# V3_0.net
KiCad netlist of a schematic drawn in Altium Designer
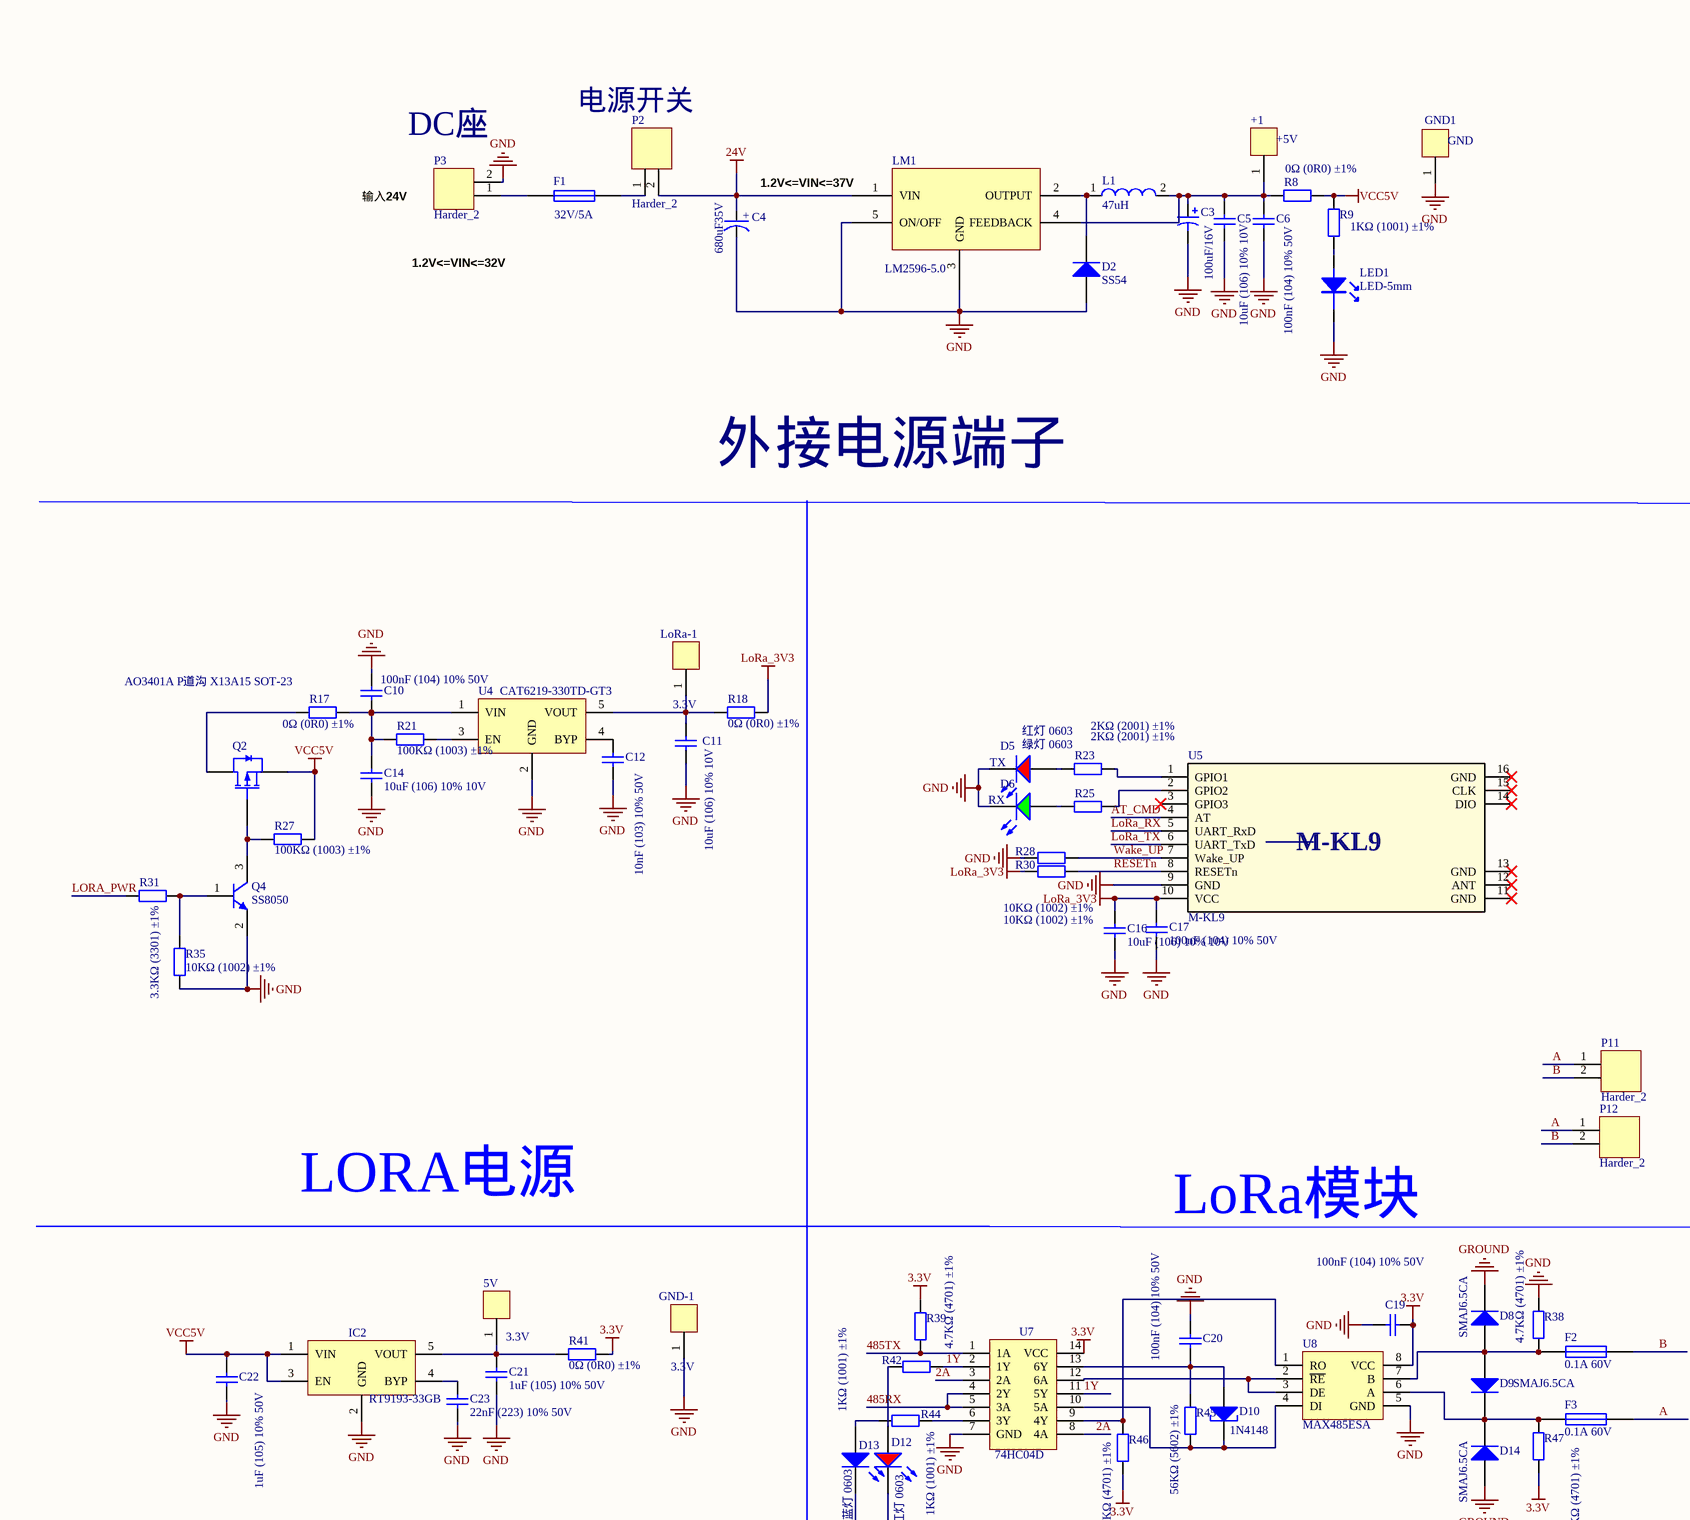
[diagram p0: 电磁阀V3.0.SchDoc, top left]
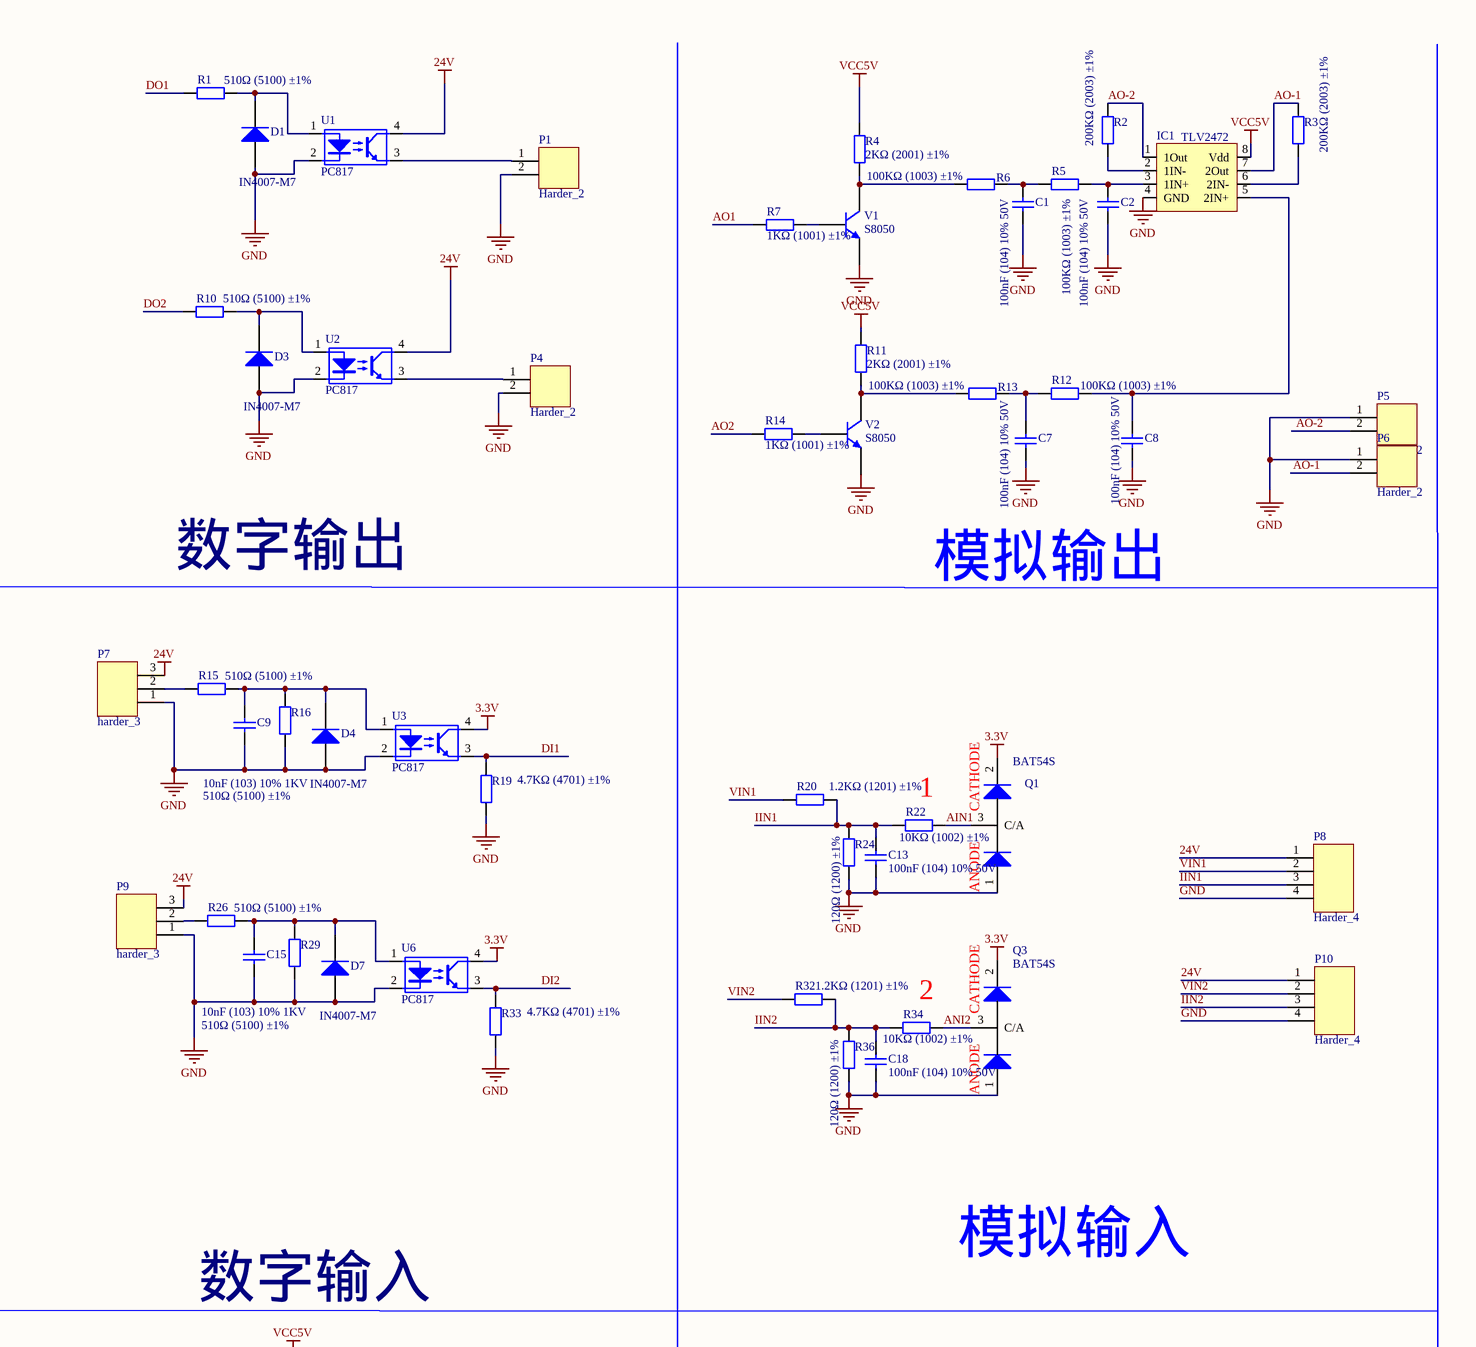
[diagram p1: 电磁阀V3.0.SchDoc, top right]
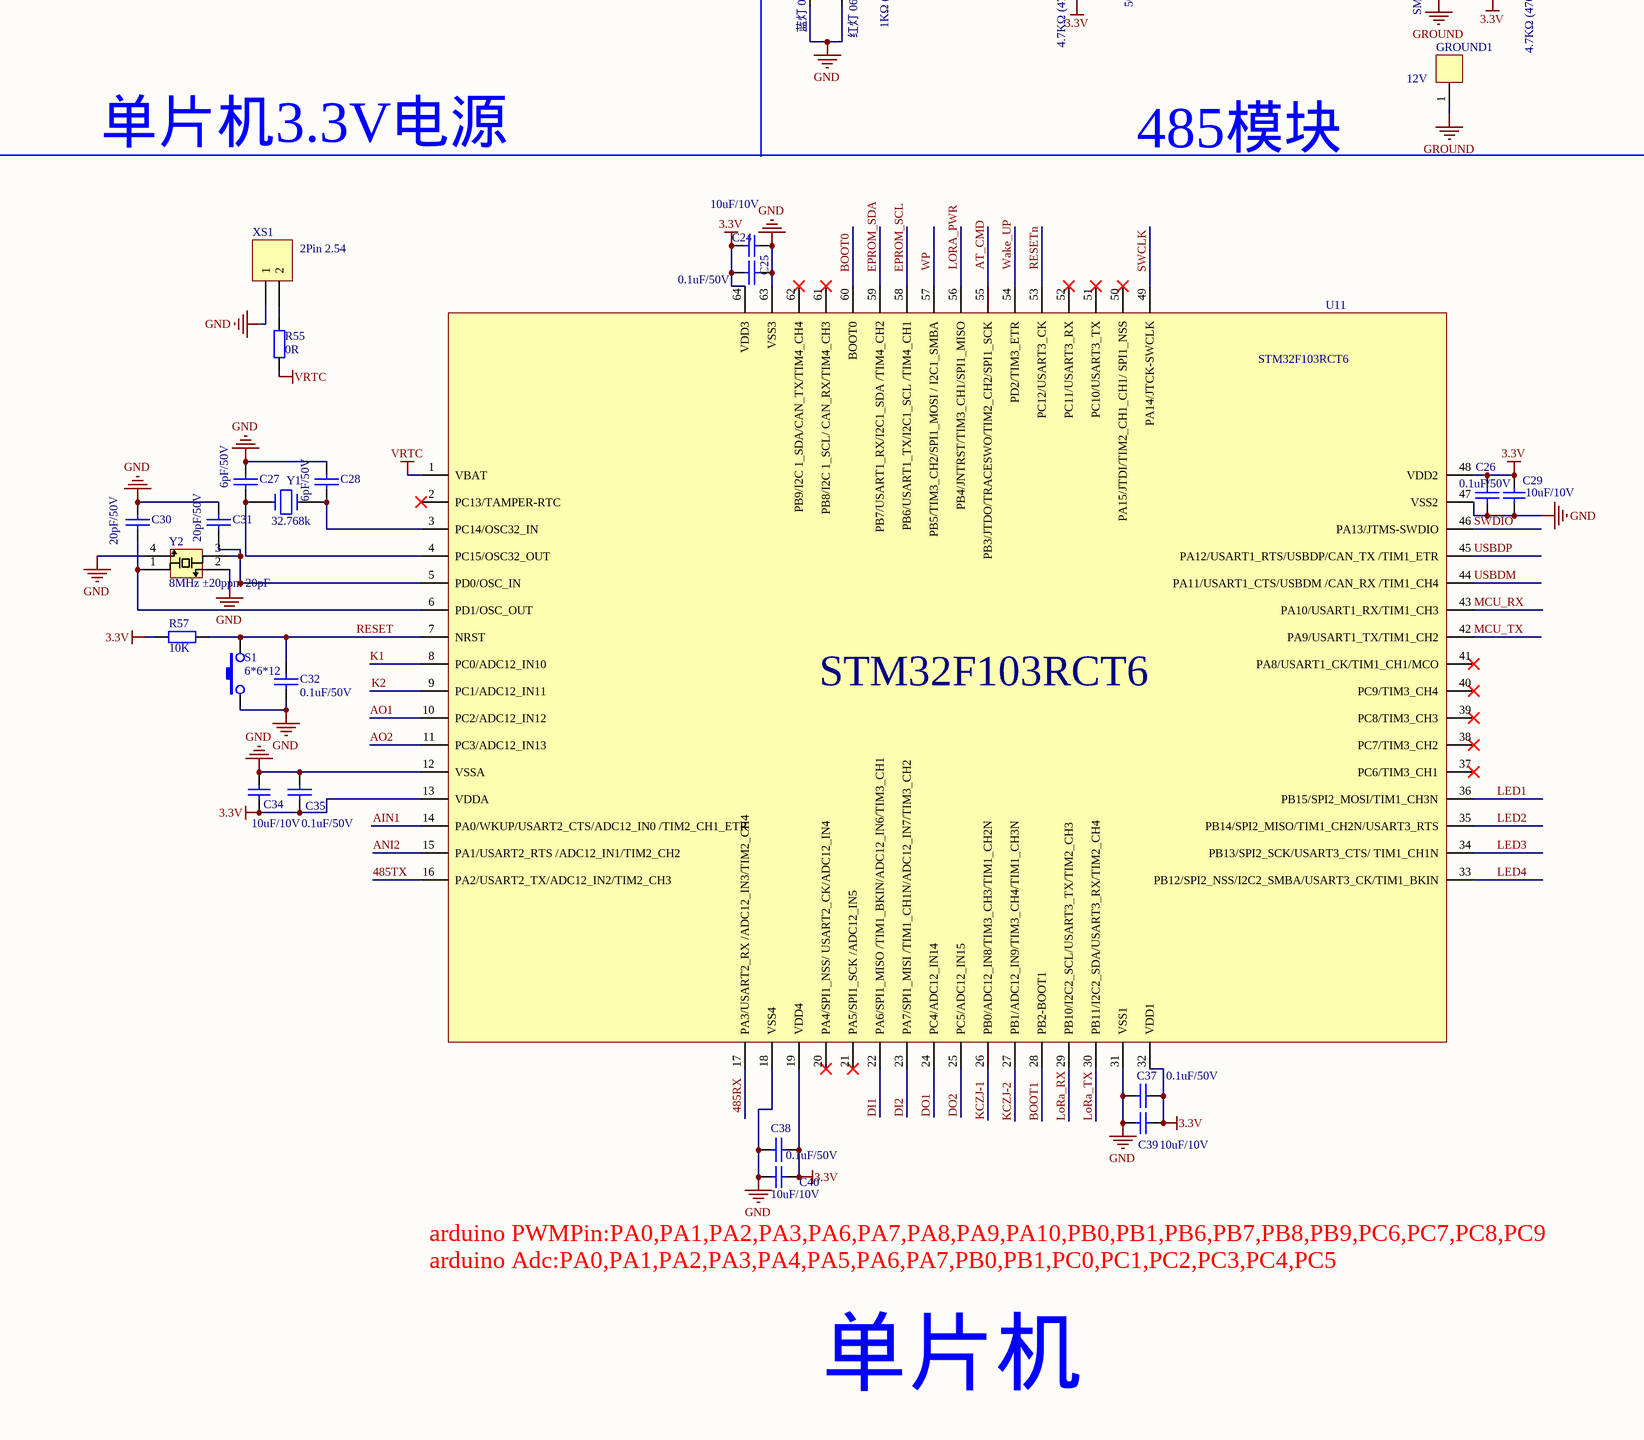
[diagram p2: 电磁阀V3.0.SchDoc, bottom left]
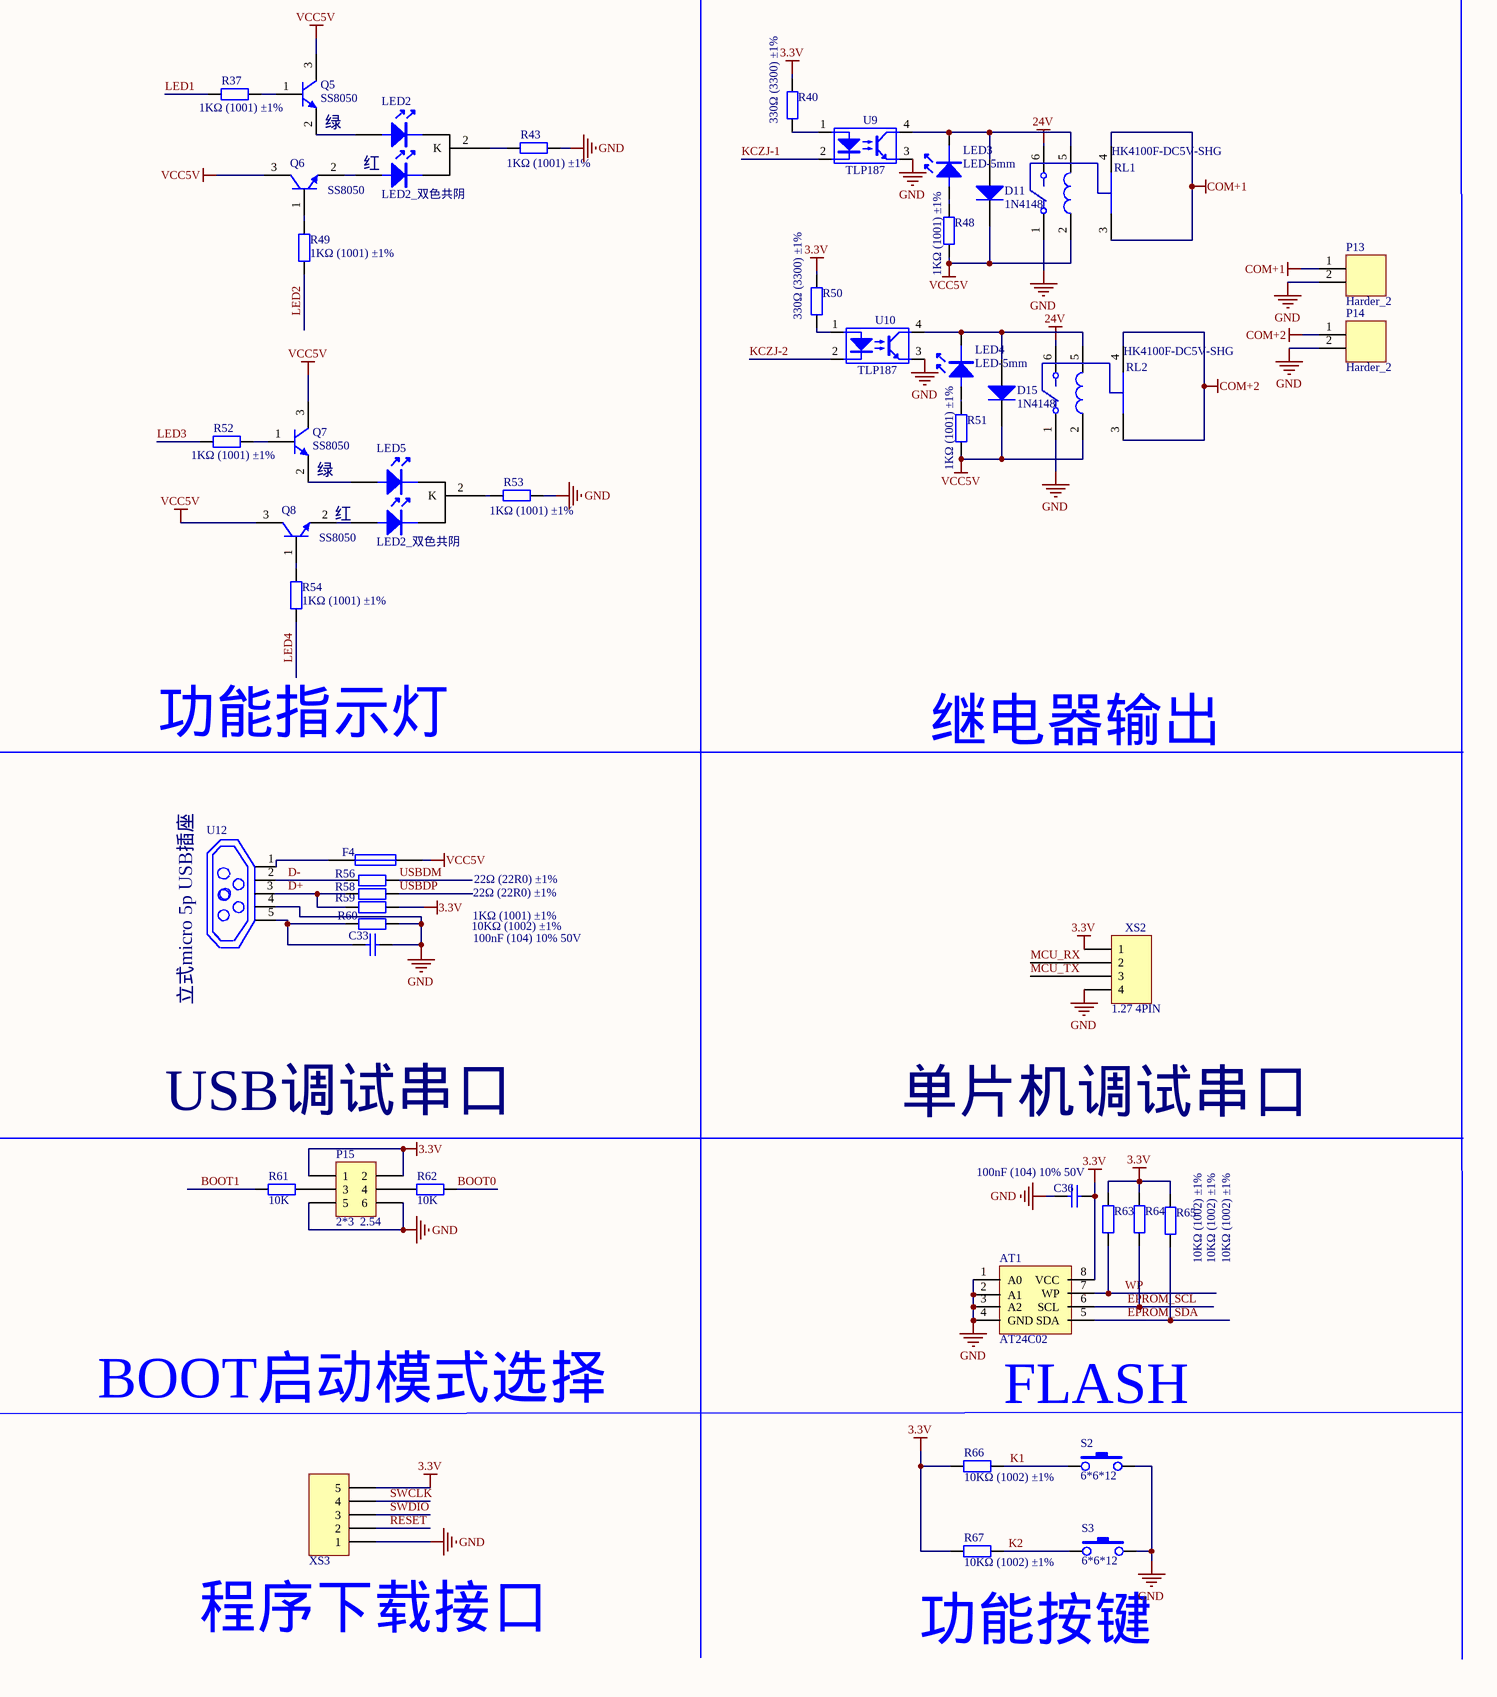
[diagram p3: 电磁阀V3.0.SchDoc, bottom right]

(export (version "E")
  (design (tool "Eeschema 10.0.6"))
  (components
    (comp (ref "+1")
      (value "+5V")
      (footprint "TEST_POINT")
      (description "测试点")
      (libsource (lib "InforCenterBoard") (part "TEST_POINT"))
    )
    (comp (ref "5V")
      (value "3.3V")
      (footprint "TEST_POINT")
      (description "测试点")
      (libsource (lib "InforCenterBoard") (part "TEST_POINT"))
    )
    (comp (ref "AT1")
      (value "AT24C02")
      (footprint "AT24C02")
      (libsource (lib "AirPlaneSign") (part "AT24C02"))
    )
    (comp (ref "C1")
      (value "100nF (104) 10% 50V")
      (footprint "LC-0603_C")
      (description "贴片电容")
      (libsource (lib "My_Library") (part "0603 100nF (104) 10% 50V"))
    )
    (comp (ref "C2")
      (value "100nF (104) 10% 50V")
      (footprint "LC-0603_C")
      (description "贴片电容")
      (libsource (lib "My_Library") (part "0603 100nF (104) 10% 50V"))
    )
    (comp (ref "C3")
      (value "100uF/16V")
      (footprint "CAP5*X")
      (description "直插电解电容")
      (fields (field (name "PUBLISHER") "Altium Limited"))
      (libsource (lib "kytence") (part "Cap Pol1"))
    )
    (comp (ref "C4") (value "680uF35V") (footprint "C10x16") (libsource (lib "My_Library") (part "CAP_DIP")))
    (comp (ref "C5")
      (value "10uF (106) 10% 10V")
      (footprint "LC-0603_C")
      (description "贴片电容")
      (libsource (lib "My_Library") (part "0603 10uF (106) 10% 10V"))
    )
    (comp (ref "C6")
      (value "100nF (104) 10% 50V")
      (footprint "LC-0603_C")
      (description "贴片电容")
      (libsource (lib "My_Library") (part "0603 100nF (104) 10% 50V"))
    )
    (comp (ref "C7")
      (value "100nF (104) 10% 50V")
      (footprint "LC-0603_C")
      (description "贴片电容")
      (libsource (lib "My_Library") (part "0603 100nF (104) 10% 50V"))
    )
    (comp (ref "C8")
      (value "100nF (104) 10% 50V")
      (footprint "LC-0603_C")
      (description "贴片电容")
      (libsource (lib "My_Library") (part "0603 100nF (104) 10% 50V"))
    )
    (comp (ref "C9")
      (value "10nF (103) 10% 1KV")
      (footprint "LC-1206_C")
      (description "贴片电容")
      (libsource (lib "My_Library") (part "1206 10nF (103) 10% 50V"))
    )
    (comp (ref "C10")
      (value "100nF (104) 10% 50V")
      (footprint "LC-0603_C")
      (description "贴片电容")
      (libsource (lib "My_Library") (part "0603 100nF (104) 10% 50V"))
    )
    (comp (ref "C11")
      (value "10uF (106) 10% 10V")
      (footprint "LC-0603_C")
      (description "贴片电容")
      (libsource (lib "My_Library") (part "0603 10uF (106) 10% 10V"))
    )
    (comp (ref "C12")
      (value "10nF (103) 10% 50V")
      (footprint "LC-0603_C")
      (description "贴片电容")
      (libsource (lib "My_Library") (part "0603 10nF (103) 10% 50V"))
    )
    (comp (ref "C13")
      (value "100nF (104) 10% 50V")
      (footprint "LC-0603_C")
      (description "贴片电容")
      (libsource (lib "My_Library") (part "0603 100nF (104) 10% 50V"))
    )
    (comp (ref "C14")
      (value "10uF (106) 10% 10V")
      (footprint "LC-0603_C")
      (description "贴片电容")
      (libsource (lib "My_Library") (part "0603 10uF (106) 10% 10V"))
    )
    (comp (ref "C15")
      (value "10nF (103) 10% 1KV")
      (footprint "LC-1206_C")
      (description "贴片电容")
      (libsource (lib "My_Library") (part "1206 10nF (103) 10% 50V"))
    )
    (comp (ref "C16")
      (value "10uF (106) 10% 10V")
      (footprint "LC-0603_C")
      (description "贴片电容")
      (libsource (lib "My_Library") (part "0603 10uF (106) 10% 10V"))
    )
    (comp (ref "C17")
      (value "100nF (104) 10% 50V")
      (footprint "LC-0603_C")
      (description "贴片电容")
      (libsource (lib "My_Library") (part "0603 100nF (104) 10% 50V"))
    )
    (comp (ref "C18")
      (value "100nF (104) 10% 50V")
      (footprint "LC-0603_C")
      (description "贴片电容")
      (libsource (lib "My_Library") (part "0603 100nF (104) 10% 50V"))
    )
    (comp (ref "C19")
      (value "100nF (104) 10% 50V")
      (footprint "LC-0603_C")
      (description "贴片电容")
      (libsource (lib "My_Library") (part "0603 100nF (104) 10% 50V"))
    )
    (comp (ref "C20")
      (value "100nF (104) 10% 50V")
      (footprint "LC-0603_C")
      (description "贴片电容")
      (libsource (lib "My_Library") (part "0603 100nF (104) 10% 50V"))
    )
    (comp (ref "C21")
      (value "1uF (105) 10% 50V")
      (footprint "LC-0603_C")
      (description "贴片电容")
      (libsource (lib "My_Library") (part "0603 1uF (105) 10% 50V"))
    )
    (comp (ref "C22")
      (value "1uF (105) 10% 50V")
      (footprint "LC-0603_C")
      (description "贴片电容")
      (libsource (lib "My_Library") (part "0603 1uF (105) 10% 50V"))
    )
    (comp (ref "C23")
      (value "22nF (223) 10% 50V")
      (footprint "LC-0603_C")
      (description "贴片电容")
      (libsource (lib "My_Library") (part "0603 22nF (223) 10% 50V"))
    )
    (comp (ref "C24")
      (value "10uF/10V")
      (footprint "C-0603")
      (description "贴片电容")
      (fields (field (name "PUBLISHER") "Altium Limited"))
      (libsource (lib "Miscellaneous Devices") (part "Cap"))
    )
    (comp (ref "C25")
      (value "0.1uF/50V")
      (footprint "C-0603")
      (description "贴片电容")
      (libsource (lib "*") (part "CAP"))
    )
    (comp (ref "C26")
      (value "0.1uF/50V")
      (footprint "C-0603")
      (description "贴片电容")
      (libsource (lib "*") (part "CAP"))
    )
    (comp (ref "C27")
      (value "6pF/50V")
      (footprint "C-0603")
      (description "贴片电容")
      (libsource (lib "*") (part "CAP"))
    )
    (comp (ref "C28")
      (value "6pF/50V")
      (footprint "C-0603")
      (description "贴片电容")
      (libsource (lib "*") (part "CAP"))
    )
    (comp (ref "C29")
      (value "10uF/10V")
      (footprint "C-0603")
      (description "贴片电容")
      (fields (field (name "PUBLISHER") "Altium Limited"))
      (libsource (lib "Miscellaneous Devices") (part "Cap"))
    )
    (comp (ref "C30")
      (value "20pF/50V")
      (footprint "C-0603")
      (description "贴片电容")
      (libsource (lib "*") (part "CAP"))
    )
    (comp (ref "C31")
      (value "20pF/50V")
      (footprint "C-0603")
      (description "贴片电容")
      (libsource (lib "*") (part "CAP"))
    )
    (comp (ref "C32")
      (value "0.1uF/50V")
      (footprint "C-0603")
      (description "贴片电容")
      (libsource (lib "*") (part "CAP"))
    )
    (comp (ref "C33")
      (value "100nF (104) 10% 50V")
      (footprint "LC-0603_C")
      (description "贴片电容")
      (libsource (lib "My_Library") (part "0603 100nF (104) 10% 50V"))
    )
    (comp (ref "C34")
      (value "10uF/10V")
      (footprint "C-0603")
      (description "贴片电容")
      (fields (field (name "PUBLISHER") "Altium Limited"))
      (libsource (lib "Miscellaneous Devices") (part "Cap"))
    )
    (comp (ref "C35")
      (value "0.1uF/50V")
      (footprint "C-0603")
      (description "贴片电容")
      (libsource (lib "*") (part "CAP"))
    )
    (comp (ref "C36")
      (value "100nF (104) 10% 50V")
      (footprint "LC-0603_C")
      (description "贴片电容")
      (libsource (lib "My_Library") (part "0603 100nF (104) 10% 50V"))
    )
    (comp (ref "C37")
      (value "0.1uF/50V")
      (footprint "C-0603")
      (description "贴片电容")
      (libsource (lib "*") (part "CAP"))
    )
    (comp (ref "C38")
      (value "0.1uF/50V")
      (footprint "C-0603")
      (description "贴片电容")
      (libsource (lib "*") (part "CAP"))
    )
    (comp (ref "C39")
      (value "10uF/10V")
      (footprint "C-0603")
      (description "贴片电容")
      (fields (field (name "PUBLISHER") "Altium Limited"))
      (libsource (lib "Miscellaneous Devices") (part "Cap"))
    )
    (comp (ref "C40")
      (value "10uF/10V")
      (footprint "C-0603")
      (description "贴片电容")
      (fields (field (name "PUBLISHER") "Altium Limited"))
      (libsource (lib "Miscellaneous Devices") (part "Cap"))
    )
    (comp (ref "D1")
      (value "IN4007-M7")
      (footprint "DO-214AC")
      (description "二极管")
      (fields (field (name "PUBLISHER") "Altium Limited"))
      (libsource (lib "Miscellaneous Devices LC") (part "Diode 1N4001"))
    )
    (comp (ref "D2")
      (value "SS54")
      (footprint "LC-SMA(DO-214AC)_S1")
      (description "二极管")
      (libsource (lib "My_Library") (part "SMA(DO-214AC) SS54"))
    )
    (comp (ref "D3")
      (value "IN4007-M7")
      (footprint "DO-214AC")
      (description "二极管")
      (fields (field (name "PUBLISHER") "Altium Limited"))
      (libsource (lib "Miscellaneous Devices LC") (part "Diode 1N4001"))
    )
    (comp (ref "D4")
      (value "IN4007-M7")
      (footprint "DO-214AC")
      (description "二极管")
      (fields (field (name "PUBLISHER") "Altium Limited"))
      (libsource (lib "Miscellaneous Devices LC") (part "Diode 1N4001"))
    )
    (comp (ref "D5")
      (value "红灯 0603")
      (footprint "LC-0603_LED_S1")
      (description "发光二极管")
      (libsource (lib "My_Library") (part "0603 红灯"))
    )
    (comp (ref "D6")
      (value "绿灯 0603")
      (footprint "LC-0603_LED_S1")
      (description "发光二极管")
      (libsource (lib "My_Library") (part "0603 绿灯"))
    )
    (comp (ref "D7")
      (value "IN4007-M7")
      (footprint "DO-214AC")
      (description "二极管")
      (fields (field (name "PUBLISHER") "Altium Limited"))
      (libsource (lib "Miscellaneous Devices LC") (part "Diode 1N4001"))
    )
    (comp (ref "D8")
      (value "SMAJ6.5CA")
      (footprint "DO-214AC")
      (description "通用二极管")
      (fields (field (name "PUBLISHER") "Altium Limited"))
      (libsource (lib "kytence") (part "Diode"))
    )
    (comp (ref "D9")
      (value "SMAJ6.5CA")
      (footprint "DO-214AC")
      (description "通用二极管")
      (fields (field (name "PUBLISHER") "Altium Limited"))
      (libsource (lib "kytence") (part "Diode"))
    )
    (comp (ref "D10")
      (value "1N4148")
      (footprint "LL-34")
      (description "稳压二极管")
      (fields (field (name "PUBLISHER") "Altium Limited"))
      (libsource (lib "Emergency lighting") (part "Diode Zener"))
    )
    (comp (ref "D11")
      (value "1N4148")
      (footprint "SOD-123")
      (description "开关二极管")
      (libsource (lib "SCHEMATIC") (part "开关二极管"))
    )
    (comp (ref "D12")
      (value "红灯 0603")
      (footprint "LC-0603_LED_S1")
      (description "发光二极管")
      (libsource (lib "My_Library") (part "0603 红灯"))
    )
    (comp (ref "D13")
      (value "蓝灯 0603")
      (footprint "LC-0603_LED_S1")
      (description "发光二极管")
      (libsource (lib "My_Library") (part "0603 蓝灯"))
    )
    (comp (ref "D14")
      (value "SMAJ6.5CA")
      (footprint "DO-214AC")
      (description "通用二极管")
      (fields (field (name "PUBLISHER") "Altium Limited"))
      (libsource (lib "kytence") (part "Diode"))
    )
    (comp (ref "D15")
      (value "1N4148")
      (footprint "SOD-123")
      (description "开关二极管")
      (libsource (lib "SCHEMATIC") (part "开关二极管"))
    )
    (comp (ref "F1")
      (value "32V/5A")
      (footprint "Fuse-1206")
      (description "贴片保险丝")
      (fields (field (name "PUBLISHER") "Altium Limited"))
      (libsource (lib "Emergency lighting") (part "Fuse"))
    )
    (comp (ref "F2")
      (value "0.1A 60V")
      (footprint "R-1812")
      (description "贴片保险丝 0.1A 60V")
      (fields (field (name "PUBLISHER") "Altium Limited"))
      (libsource (lib "AirPlaneSign") (part "Fuse_1"))
    )
    (comp (ref "F3")
      (value "0.1A 60V")
      (footprint "R-1812")
      (description "贴片保险丝 0.1A 60V")
      (fields (field (name "PUBLISHER") "Altium Limited"))
      (libsource (lib "AirPlaneSign") (part "Fuse_1"))
    )
    (comp (ref "F4")
      (value "32V/5A")
      (footprint "FUSE-1206")
      (description "贴片保险丝")
      (fields (field (name "PUBLISHER") "Altium Limited"))
      (libsource (lib "AirPlaneSign") (part "Fuse"))
    )
    (comp (ref "GND-1")
      (value "3.3V")
      (footprint "TEST_POINT")
      (description "测试点")
      (libsource (lib "InforCenterBoard") (part "TEST_POINT"))
    )
    (comp (ref "GND1")
      (value "GND")
      (footprint "TEST_POINT")
      (description "测试点")
      (libsource (lib "InforCenterBoard") (part "TEST_POINT"))
    )
    (comp (ref "GROUND1")
      (value "12V")
      (footprint "TEST_POINT")
      (description "测试点")
      (libsource (lib "InforCenterBoard") (part "TEST_POINT"))
    )
    (comp (ref "IC1")
      (value "TLV2472")
      (footprint "SOP8")
      (description "输出放大")
      (libsource (lib "Arduino-PLC") (part "TLV2472"))
    )
    (comp (ref "IC2")
      (value "RT9193-33GB")
      (footprint "SOT23-5")
      (description "低压差线性稳压(LDO)")
      (libsource (lib "FM") (part "CAT6219"))
    )
    (comp (ref "L1")
      (value "47uH")
      (footprint "SMD,13.8x12.6x7mm")
      (description "4R7功率电感")
      (fields (field (name "Comment") "47uH ±20%") (field (name "PUBLISHER") "Altium Limited"))
      (libsource (lib "AirPlaneSign") (part "47uH ±20%"))
    )
    (comp (ref "LED1")
      (value "LED-5mm")
      (footprint "LED_5mm")
      (description "发光二极管")
      (libsource (lib "AirPlaneSign") (part "LED-5mm"))
    )
    (comp (ref "LED2")
      (value "LED2_双色共阴")
      (footprint "双色LED")
      (libsource (lib "AirPlaneSign") (part "LED2_双色共阴"))
    )
    (comp (ref "LED3")
      (value "LED-5mm")
      (footprint "LED_5mm")
      (description "发光二极管")
      (libsource (lib "AirPlaneSign") (part "LED-5mm"))
    )
    (comp (ref "LED4")
      (value "LED-5mm")
      (footprint "LED_5mm")
      (description "发光二极管")
      (libsource (lib "AirPlaneSign") (part "LED-5mm"))
    )
    (comp (ref "LED5")
      (value "LED2_双色共阴")
      (footprint "双色LED")
      (libsource (lib "AirPlaneSign") (part "LED2_双色共阴"))
    )
    (comp (ref "LM1") (value "LM2596-5.0") (footprint "LC-TO-263-5") (libsource (lib "LZH") (part "LM2596")))
    (comp (ref "LoRa-1")
      (value "3.3V")
      (footprint "TEST_POINT")
      (description "测试点")
      (libsource (lib "InforCenterBoard") (part "TEST_POINT"))
    )
    (comp (ref "P1")
      (value "Harder_2")
      (footprint "2Pin-2.54A")
      (libsource (lib "My_Library") (part "Harder_2"))
    )
    (comp (ref "P2") (value "Harder_2") (footprint "2Pin-2.54A") (libsource (lib "") (part "Harder_2_1")))
    (comp (ref "P3") (value "Harder_2") (footprint "2Pin-2.54A") (libsource (lib "") (part "Harder_2_2")))
    (comp (ref "P4")
      (value "Harder_2")
      (footprint "2Pin-2.54A")
      (libsource (lib "My_Library") (part "Harder_2"))
    )
    (comp (ref "P5")
      (value "Harder_2")
      (footprint "2Pin-2.54A")
      (libsource (lib "My_Library") (part "Harder_2"))
    )
    (comp (ref "P6")
      (value "Harder_2")
      (footprint "2Pin-2.54A")
      (libsource (lib "My_Library") (part "Harder_2"))
    )
    (comp (ref "P7")
      (value "harder_3")
      (footprint "3PIN-2.54")
      (libsource (lib "My_Library") (part "harder_3"))
    )
    (comp (ref "P8")
      (value "Harder_4")
      (footprint "4PIN-2.54 A")
      (libsource (lib "My_Library") (part "Harder_4"))
    )
    (comp (ref "P9")
      (value "harder_3")
      (footprint "3PIN-2.54")
      (libsource (lib "My_Library") (part "harder_3"))
    )
    (comp (ref "P10")
      (value "Harder_4")
      (footprint "4PIN-2.54 A")
      (libsource (lib "My_Library") (part "Harder_4"))
    )
    (comp (ref "P11")
      (value "Harder_2")
      (footprint "2Pin-2.54A")
      (libsource (lib "My_Library") (part "Harder_2"))
    )
    (comp (ref "P12")
      (value "Harder_2")
      (footprint "2Pin-2.54A")
      (libsource (lib "My_Library") (part "Harder_2"))
    )
    (comp (ref "P13")
      (value "Harder_2")
      (footprint "2Pin-2.54A")
      (libsource (lib "My_Library") (part "Harder_2"))
    )
    (comp (ref "P14")
      (value "Harder_2")
      (footprint "2Pin-2.54A")
      (libsource (lib "My_Library") (part "Harder_2"))
    )
    (comp (ref "P15")
      (value "2*3  2.54")
      (footprint "201S2X3")
      (description "双排插针")
      (fields (field (name "PUBLISHER") "Altium Limited"))
      (libsource (lib "AirPlaneSign") (part "Header 2*3"))
    )
    (comp (ref "Q1")
      (value "BAT54S")
      (footprint "SOT-23-3")
      (description "肖特基二极管")
      (libsource (lib "AirPlaneSign") (part "BAT54S"))
    )
    (comp (ref "Q2")
      (value "AO3401A P道沟 X13A15 SOT-23")
      (footprint "LC-SOT-23-3L")
      (description "MOS(场效应管)")
      (libsource (lib "My_Library") (part "AO3401A P道沟 X13A15 SOT-23"))
    )
    (comp (ref "Q3")
      (value "BAT54S")
      (footprint "SOT-23-3")
      (description "肖特基二极管")
      (libsource (lib "AirPlaneSign") (part "BAT54S"))
    )
    (comp (ref "Q4")
      (value "SS8050")
      (footprint "SOT-23")
      (description "NPN贴片三极管")
      (fields (field (name "PUBLISHER") "Altium Limited"))
      (libsource (lib "My_Library") (part "SS8050"))
    )
    (comp (ref "Q5")
      (value "SS8050")
      (footprint "SOT-23")
      (description "NPN贴片三极管")
      (fields (field (name "PUBLISHER") "Altium Limited"))
      (libsource (lib "My_Library") (part "SS8050"))
    )
    (comp (ref "Q6")
      (value "SS8050")
      (footprint "SOT-23")
      (description "NPN贴片三极管")
      (fields (field (name "PUBLISHER") "Altium Limited"))
      (libsource (lib "My_Library") (part "SS8050"))
    )
    (comp (ref "Q7")
      (value "SS8050")
      (footprint "SOT-23")
      (description "NPN贴片三极管")
      (fields (field (name "PUBLISHER") "Altium Limited"))
      (libsource (lib "My_Library") (part "SS8050"))
    )
    (comp (ref "Q8")
      (value "SS8050")
      (footprint "SOT-23")
      (description "NPN贴片三极管")
      (fields (field (name "PUBLISHER") "Altium Limited"))
      (libsource (lib "My_Library") (part "SS8050"))
    )
    (comp (ref "R1")
      (value "510Ω (5100) ±1%")
      (footprint "LC-0603_R")
      (description "贴片电阻")
      (libsource (lib "") (part "0603 510Ω (5100) 1%_1"))
    )
    (comp (ref "R2")
      (value "200KΩ (2003) ±1%")
      (footprint "LC-0603_R")
      (description "贴片电阻")
      (libsource (lib "My_Library") (part "0603 200KΩ (2003) 1%"))
    )
    (comp (ref "R3")
      (value "200KΩ (2003) ±1%")
      (footprint "LC-0603_R")
      (description "贴片电阻")
      (libsource (lib "My_Library") (part "0603 200KΩ (2003) 1%"))
    )
    (comp (ref "R4")
      (value "2KΩ (2001) ±1%")
      (footprint "LC-0603_R")
      (description "贴片电阻")
      (libsource (lib "") (part "0603 2KΩ (2001) 1%_1"))
    )
    (comp (ref "R5")
      (value "100KΩ (1003) ±1%")
      (footprint "LC-0603_R")
      (description "贴片电阻")
      (libsource (lib "My_Library") (part "0603 100KΩ (1003) 1%"))
    )
    (comp (ref "R6")
      (value "100KΩ (1003) ±1%")
      (footprint "LC-0603_R")
      (description "贴片电阻")
      (libsource (lib "My_Library") (part "0603 100KΩ (1003) 1%"))
    )
    (comp (ref "R7")
      (value "1KΩ (1001) ±1%")
      (footprint "LC-0603_R")
      (description "贴片电阻")
      (libsource (lib "") (part "0603 1KΩ (1001) 1%_1"))
    )
    (comp (ref "R8")
      (value "0Ω (0R0) ±1%")
      (footprint "LC-0603_R")
      (description "贴片电阻")
      (libsource (lib "My_Library") (part "0603 0Ω (0R0) 1%"))
    )
    (comp (ref "R9")
      (value "1KΩ (1001) ±1%")
      (footprint "LC-0603_R")
      (description "贴片电阻")
      (libsource (lib "My_Library") (part "0603 1KΩ (1001) 1%"))
    )
    (comp (ref "R10")
      (value "510Ω (5100) ±1%")
      (footprint "LC-0603_R")
      (description "贴片电阻")
      (libsource (lib "") (part "0603 510Ω (5100) 1%_1"))
    )
    (comp (ref "R11")
      (value "2KΩ (2001) ±1%")
      (footprint "LC-0603_R")
      (description "贴片电阻")
      (libsource (lib "") (part "0603 2KΩ (2001) 1%_1"))
    )
    (comp (ref "R12")
      (value "100KΩ (1003) ±1%")
      (footprint "LC-0603_R")
      (description "贴片电阻")
      (libsource (lib "My_Library") (part "0603 100KΩ (1003) 1%"))
    )
    (comp (ref "R13")
      (value "100KΩ (1003) ±1%")
      (footprint "LC-0603_R")
      (description "贴片电阻")
      (libsource (lib "My_Library") (part "0603 100KΩ (1003) 1%"))
    )
    (comp (ref "R14")
      (value "1KΩ (1001) ±1%")
      (footprint "LC-0603_R")
      (description "贴片电阻")
      (libsource (lib "") (part "0603 1KΩ (1001) 1%_1"))
    )
    (comp (ref "R15")
      (value "510Ω (5100) ±1%")
      (footprint "LC-0603_R")
      (description "贴片电阻")
      (libsource (lib "") (part "0603 510Ω (5100) 1%_1"))
    )
    (comp (ref "R16")
      (value "510Ω (5100) ±1%")
      (footprint "LC-0603_R")
      (description "贴片电阻")
      (libsource (lib "My_Library") (part "0603 510Ω (5100) 1%"))
    )
    (comp (ref "R17")
      (value "0Ω (0R0) ±1%")
      (footprint "LC-0603_R")
      (description "贴片电阻")
      (libsource (lib "My_Library") (part "0603 0Ω (0R0) 1%"))
    )
    (comp (ref "R18")
      (value "0Ω (0R0) ±1%")
      (footprint "LC-0603_R")
      (description "贴片电阻")
      (libsource (lib "My_Library") (part "0603 0Ω (0R0) 1%"))
    )
    (comp (ref "R19")
      (value "4.7KΩ (4701) ±1%")
      (footprint "LC-0603_R")
      (description "贴片电阻")
      (libsource (lib "My_Library") (part "0603 4.7KΩ (4701) 1%"))
    )
    (comp (ref "R20")
      (value "1.2KΩ (1201) ±1%")
      (footprint "LC-0603_R")
      (description "贴片电阻")
      (libsource (lib "My_Library") (part "0603 1.2KΩ (1201) 1%"))
    )
    (comp (ref "R21")
      (value "100KΩ (1003) ±1%")
      (footprint "LC-0603_R")
      (description "贴片电阻")
      (libsource (lib "My_Library") (part "0603 100KΩ (1003) 1%"))
    )
    (comp (ref "R22")
      (value "10KΩ (1002) ±1%")
      (footprint "LC-0603_R")
      (description "贴片电阻")
      (libsource (lib "My_Library") (part "0603 10KΩ (1002) 1%"))
    )
    (comp (ref "R23")
      (value "2KΩ (2001) ±1%")
      (footprint "LC-0603_R")
      (description "贴片电阻")
      (libsource (lib "My_Library") (part "0603 2KΩ (2001) 1%"))
    )
    (comp (ref "R24")
      (value "120Ω (1200) ±1%")
      (footprint "LC-0603_R")
      (description "贴片电阻")
      (libsource (lib "My_Library") (part "0603 120Ω (1200) 1%"))
    )
    (comp (ref "R25")
      (value "2KΩ (2001) ±1%")
      (footprint "LC-0603_R")
      (description "贴片电阻")
      (libsource (lib "My_Library") (part "0603 2KΩ (2001) 1%"))
    )
    (comp (ref "R26")
      (value "510Ω (5100) ±1%")
      (footprint "LC-0603_R")
      (description "贴片电阻")
      (libsource (lib "") (part "0603 510Ω (5100) 1%_1"))
    )
    (comp (ref "R27")
      (value "100KΩ (1003) ±1%")
      (footprint "LC-0603_R")
      (description "贴片电阻")
      (libsource (lib "E32-TTL_LoRa_SENSOR-V3.0") (part "0603 100KΩ (1003) 1%"))
    )
    (comp (ref "R28")
      (value "10KΩ (1002) ±1%")
      (footprint "LC-0603_R")
      (description "贴片电阻")
      (libsource (lib "My_Library") (part "0603 10KΩ (1002) 1%"))
    )
    (comp (ref "R29")
      (value "510Ω (5100) ±1%")
      (footprint "LC-0603_R")
      (description "贴片电阻")
      (libsource (lib "My_Library") (part "0603 510Ω (5100) 1%"))
    )
    (comp (ref "R30")
      (value "10KΩ (1002) ±1%")
      (footprint "LC-0603_R")
      (description "贴片电阻")
      (libsource (lib "My_Library") (part "0603 10KΩ (1002) 1%"))
    )
    (comp (ref "R31")
      (value "3.3KΩ (3301) ±1%")
      (footprint "LC-0603_R")
      (description "贴片电阻")
      (libsource (lib "My_Library") (part "0603 3.3KΩ (3301) 1%"))
    )
    (comp (ref "R32")
      (value "1.2KΩ (1201) ±1%")
      (footprint "LC-0603_R")
      (description "贴片电阻")
      (libsource (lib "My_Library") (part "0603 1.2KΩ (1201) 1%"))
    )
    (comp (ref "R33")
      (value "4.7KΩ (4701) ±1%")
      (footprint "LC-0603_R")
      (description "贴片电阻")
      (libsource (lib "My_Library") (part "0603 4.7KΩ (4701) 1%"))
    )
    (comp (ref "R34")
      (value "10KΩ (1002) ±1%")
      (footprint "LC-0603_R")
      (description "贴片电阻")
      (libsource (lib "My_Library") (part "0603 10KΩ (1002) 1%"))
    )
    (comp (ref "R35")
      (value "10KΩ (1002) ±1%")
      (footprint "LC-0603_R")
      (description "贴片电阻")
      (libsource (lib "") (part "0603 10KΩ (1002) 1%_1"))
    )
    (comp (ref "R36")
      (value "120Ω (1200) ±1%")
      (footprint "LC-0603_R")
      (description "贴片电阻")
      (libsource (lib "My_Library") (part "0603 120Ω (1200) 1%"))
    )
    (comp (ref "R37")
      (value "1KΩ (1001) ±1%")
      (footprint "LC-0603_R")
      (description "贴片电阻")
      (libsource (lib "") (part "0603 1KΩ (1001) 1%_1"))
    )
    (comp (ref "R38")
      (value "4.7KΩ (4701) ±1%")
      (footprint "LC-0603_R")
      (description "贴片电阻")
      (libsource (lib "") (part "0603 4.7KΩ (4701) 1%_1"))
    )
    (comp (ref "R39")
      (value "4.7KΩ (4701) ±1%")
      (footprint "LC-0603_R")
      (description "贴片电阻")
      (libsource (lib "My_Library") (part "0603 4.7KΩ (4701) 1%"))
    )
    (comp (ref "R40")
      (value "330Ω (3300) ±1%")
      (footprint "LC-0603_R")
      (description "贴片电阻")
      (libsource (lib "My_Library") (part "0603 330Ω (3300) 1%"))
    )
    (comp (ref "R41")
      (value "0Ω (0R0) ±1%")
      (footprint "LC-0603_R")
      (description "贴片电阻")
      (libsource (lib "My_Library") (part "0603 0Ω (0R0) 1%"))
    )
    (comp (ref "R42")
      (value "1KΩ (1001) ±1%")
      (footprint "LC-0603_R")
      (description "贴片电阻")
      (libsource (lib "") (part "0603 1KΩ (1001) 1%_1"))
    )
    (comp (ref "R43")
      (value "1KΩ (1001) ±1%")
      (footprint "LC-0603_R")
      (description "贴片电阻")
      (libsource (lib "") (part "0603 1KΩ (1001) 1%_2"))
    )
    (comp (ref "R44")
      (value "1KΩ (1001) ±1%")
      (footprint "LC-0603_R")
      (description "贴片电阻")
      (libsource (lib "") (part "0603 1KΩ (1001) 1%_1"))
    )
    (comp (ref "R45")
      (value "56KΩ (5602) ±1%")
      (footprint "LC-0603_R")
      (description "贴片电阻")
      (libsource (lib "My_Library") (part "0603 56KΩ (5602) 1%"))
    )
    (comp (ref "R46")
      (value "4.7KΩ (4701) ±1%")
      (footprint "LC-0603_R")
      (description "贴片电阻")
      (libsource (lib "My_Library") (part "0603 4.7KΩ (4701) 1%"))
    )
    (comp (ref "R47")
      (value "4.7KΩ (4701) ±1%")
      (footprint "LC-0603_R")
      (description "贴片电阻")
      (libsource (lib "My_Library") (part "0603 4.7KΩ (4701) 1%"))
    )
    (comp (ref "R48")
      (value "1KΩ (1001) ±1%")
      (footprint "LC-0603_R")
      (description "贴片电阻")
      (libsource (lib "") (part "0603 1KΩ (1001) 1%_3"))
    )
    (comp (ref "R49")
      (value "1KΩ (1001) ±1%")
      (footprint "LC-0603_R")
      (description "贴片电阻")
      (libsource (lib "My_Library") (part "0603 1KΩ (1001) 1%"))
    )
    (comp (ref "R50")
      (value "330Ω (3300) ±1%")
      (footprint "LC-0603_R")
      (description "贴片电阻")
      (libsource (lib "My_Library") (part "0603 330Ω (3300) 1%"))
    )
    (comp (ref "R51")
      (value "1KΩ (1001) ±1%")
      (footprint "LC-0603_R")
      (description "贴片电阻")
      (libsource (lib "") (part "0603 1KΩ (1001) 1%_3"))
    )
    (comp (ref "R52")
      (value "1KΩ (1001) ±1%")
      (footprint "LC-0603_R")
      (description "贴片电阻")
      (libsource (lib "") (part "0603 1KΩ (1001) 1%_1"))
    )
    (comp (ref "R53")
      (value "1KΩ (1001) ±1%")
      (footprint "LC-0603_R")
      (description "贴片电阻")
      (libsource (lib "") (part "0603 1KΩ (1001) 1%_2"))
    )
    (comp (ref "R54")
      (value "1KΩ (1001) ±1%")
      (footprint "LC-0603_R")
      (description "贴片电阻")
      (libsource (lib "My_Library") (part "0603 1KΩ (1001) 1%"))
    )
    (comp (ref "R55")
      (value "0R")
      (footprint "R-0603")
      (description "贴片电阻")
      (fields (field (name "PUBLISHER") "Altium Limited"))
      (libsource (lib "") (part "Res2_1"))
    )
    (comp (ref "R56")
      (value "22Ω (22R0) ±1%")
      (footprint "LC-0603_R")
      (description "贴片电阻")
      (libsource (lib "My_Library") (part "0603 22Ω (22R0) 1%"))
    )
    (comp (ref "R57")
      (value "10K")
      (footprint "R-0603")
      (description "贴片电阻")
      (fields (field (name "PUBLISHER") "Altium Limited"))
      (libsource (lib "") (part "Res2_2"))
    )
    (comp (ref "R58")
      (value "22Ω (22R0) ±1%")
      (footprint "LC-0603_R")
      (description "贴片电阻")
      (libsource (lib "My_Library") (part "0603 22Ω (22R0) 1%"))
    )
    (comp (ref "R59")
      (value "1KΩ (1001) ±1%")
      (footprint "LC-0603_R")
      (description "贴片电阻")
      (libsource (lib "") (part "0603 1KΩ (1001) 1%_1"))
    )
    (comp (ref "R60")
      (value "10KΩ (1002) ±1%")
      (footprint "LC-0603_R")
      (description "贴片电阻")
      (libsource (lib "") (part "0603 10KΩ (1002) 1%_2"))
    )
    (comp (ref "R61")
      (value "10K")
      (footprint "R-0603")
      (description "贴片电阻")
      (fields (field (name "PUBLISHER") "Altium Limited"))
      (libsource (lib "Miscellaneous Devices") (part "Res2"))
    )
    (comp (ref "R62")
      (value "10K")
      (footprint "R-0603")
      (description "贴片电阻")
      (fields (field (name "PUBLISHER") "Altium Limited"))
      (libsource (lib "Miscellaneous Devices") (part "Res2"))
    )
    (comp (ref "R63")
      (value "10KΩ (1002) ±1%")
      (footprint "LC-0603_R")
      (description "贴片电阻")
      (libsource (lib "") (part "0603 10KΩ (1002) 1%_1"))
    )
    (comp (ref "R64")
      (value "10KΩ (1002) ±1%")
      (footprint "LC-0603_R")
      (description "贴片电阻")
      (libsource (lib "") (part "0603 10KΩ (1002) 1%_1"))
    )
    (comp (ref "R65")
      (value "10KΩ (1002) ±1%")
      (footprint "LC-0603_R")
      (description "贴片电阻")
      (libsource (lib "") (part "0603 10KΩ (1002) 1%_1"))
    )
    (comp (ref "R66")
      (value "10KΩ (1002) ±1%")
      (footprint "LC-0603_R")
      (description "贴片电阻")
      (libsource (lib "My_Library") (part "0603 10KΩ (1002) 1%"))
    )
    (comp (ref "R67")
      (value "10KΩ (1002) ±1%")
      (footprint "LC-0603_R")
      (description "贴片电阻")
      (libsource (lib "My_Library") (part "0603 10KΩ (1002) 1%"))
    )
    (comp (ref "RL1")
      (value "HK4100F-DC5V-SHG")
      (footprint "HK4100F-DC5V-SHG")
      (description "继电器")
      (fields (field (name "PUBLISHER") "Altium Limited"))
      (libsource (lib "AirPlaneSign") (part "HK4100F-DC5V-SHG"))
    )
    (comp (ref "RL2")
      (value "HK4100F-DC5V-SHG")
      (footprint "HK4100F-DC5V-SHG")
      (description "继电器")
      (fields (field (name "PUBLISHER") "Altium Limited"))
      (libsource (lib "AirPlaneSign") (part "HK4100F-DC5V-SHG"))
    )
    (comp (ref "S1")
      (value "6*6*12")
      (footprint "KEY-7.0*7.0")
      (description "侧脚带支架 微型按键")
      (libsource (lib "AirPlaneSign") (part "SW-PB_4"))
    )
    (comp (ref "S2")
      (value "6*6*12")
      (footprint "KEY-7.0*7.0")
      (description "侧脚带支架 微型按键")
      (libsource (lib "AirPlaneSign") (part "SW-PB_4"))
    )
    (comp (ref "S3")
      (value "6*6*12")
      (footprint "KEY-7.0*7.0")
      (description "侧脚带支架 微型按键")
      (libsource (lib "AirPlaneSign") (part "SW-PB_4"))
    )
    (comp (ref "U1")
      (value "PC817")
      (footprint "LC-SMD-4")
      (description "光藕")
      (libsource (lib "AirPlaneSign") (part "PC817"))
    )
    (comp (ref "U2")
      (value "PC817")
      (footprint "LC-SMD-4")
      (description "光藕")
      (libsource (lib "AirPlaneSign") (part "PC817"))
    )
    (comp (ref "U3")
      (value "PC817")
      (footprint "LC-SMD-4")
      (description "光藕")
      (libsource (lib "AirPlaneSign") (part "PC817"))
    )
    (comp (ref "U4")
      (value "CAT6219-330TD-GT3")
      (footprint "SOT23-5")
      (description "CAT6219")
      (libsource (lib "My_Library") (part "CAT6219"))
    )
    (comp (ref "U5") (value "M-KL9") (footprint "M-KL9") (libsource (lib "AirPlaneSign") (part "M-KL9")))
    (comp (ref "U6")
      (value "PC817")
      (footprint "LC-SMD-4")
      (description "光藕")
      (libsource (lib "AirPlaneSign") (part "PC817"))
    )
    (comp (ref "U7")
      (value "74HC04D")
      (footprint "SOIC-14_150mil")
      (description "6路施密特触发反相器")
      (fields (field (name "PUBLISHER") "Altium Limited"))
      (libsource (lib "AirPlaneSign") (part "74HC14"))
    )
    (comp (ref "U8")
      (value "MAX485ESA")
      (footprint "SOP-8_150mil")
      (description "RS485收发芯片")
      (libsource (lib "AirPlaneSign") (part "MAX485ESA"))
    )
    (comp (ref "U9")
      (value "TLP187")
      (footprint "TLP187 - duplicate")
      (description "光藕")
      (libsource (lib "ControllerBoard") (part "Q817"))
    )
    (comp (ref "U10")
      (value "TLP187")
      (footprint "TLP187 - duplicate")
      (description "光藕")
      (libsource (lib "ControllerBoard") (part "Q817"))
    )
    (comp (ref "U11")
      (value "STM32F103RCT6")
      (footprint "LQFP-64_10x10x05P")
      (description "单片机")
      (libsource (lib "AirPlaneSign") (part "STM32F103RCT6"))
    )
    (comp (ref "U12")
      (value "立式micro 5p USB插座")
      (footprint "USB插座 micro 5p")
      (libsource (lib "AirPlaneSign") (part "USB_micro_5p"))
    )
    (comp (ref "V1")
      (value "S8050")
      (footprint "SOT-23-3")
      (description "NPN三极管")
      (fields (field (name "PUBLISHER") "Altium Limited"))
      (libsource (lib "AirPlaneSign") (part "NPN"))
    )
    (comp (ref "V2")
      (value "S8050")
      (footprint "SOT-23-3")
      (description "NPN三极管")
      (fields (field (name "PUBLISHER") "Altium Limited"))
      (libsource (lib "AirPlaneSign") (part "NPN"))
    )
    (comp (ref "XS1")
      (value "2Pin 2.54")
      (footprint "JXT-2")
      (description "单排插针")
      (fields (field (name "PUBLISHER") "Altium Limited"))
      (libsource (lib "AirPlaneSign") (part "Header 2H"))
    )
    (comp (ref "XS2")
      (value "1.27 4PIN")
      (footprint "JXT-4")
      (description "1.27卧式贴片针座")
      (fields (field (name "PUBLISHER") "Altium Limited"))
      (libsource (lib "Miscellaneous Connectors") (part "Header 4"))
    )
    (comp (ref "XS3")
      (value "Header 2.54X4")
      (footprint "JXT-5")
      (description "1.27卧式贴片针座")
      (fields (field (name "PUBLISHER") "Altium Limited"))
      (libsource (lib "AirPlaneSign") (part "Header 5"))
    )
    (comp (ref "Y1")
      (value "32.768k")
      (footprint "3215_32.768K")
      (description "Crystal")
      (libsource (lib "Device Library") (part "CRYSTAL"))
    )
    (comp (ref "Y2")
      (value "8MHz ±20ppm 20pF")
      (footprint "LC-SMD-5032_4P")
      (description "贴片晶振")
      (libsource (lib "AirPlaneSign") (part "SMD-5032_4P 8MHz 20ppm 20pF"))
    )
  )
  (nets
    (net (code "1") (name "/1Y") (class "Default")
      (node (ref "R42") (pin "2") (pinfunction "2_2") (pintype "passive"))
      (node (ref "U7") (pin "11") (pinfunction "5Y_11") (pintype "passive"))
      (node (ref "U7") (pin "2") (pinfunction "1Y_2") (pintype "passive"))
    )
    (net (code "2") (name "/2A") (class "Default")
      (node (ref "U7") (pin "3") (pinfunction "2A_3") (pintype "passive"))
      (node (ref "U7") (pin "8") (pinfunction "4A_8") (pintype "passive"))
    )
    (net (code "3") (name "/485RX") (class "Default")
      (node (ref "U11") (pin "17") (pinfunction "PA3/USART2_RX_/ADC12_IN3/TIM2_CH4_17") (pintype "passive"))
      (node (ref "U7") (pin "4") (pinfunction "2Y_4") (pintype "passive"))
      (node (ref "U7") (pin "5") (pinfunction "3A_5") (pintype "passive"))
    )
    (net (code "4") (name "/485TX") (class "Default")
      (node (ref "R39") (pin "1") (pinfunction "1_1") (pintype "passive"))
      (node (ref "U11") (pin "16") (pinfunction "PA2/USART2_TX/ADC12_IN2/TIM2_CH3_16") (pintype "passive"))
      (node (ref "U7") (pin "1") (pinfunction "1A_1") (pintype "passive"))
    )
    (net (code "5") (name "/A") (class "Default")
      (node (ref "F3") (pin "2") (pinfunction "2_2") (pintype "passive"))
      (node (ref "P11") (pin "1") (pinfunction "1_1") (pintype "passive"))
      (node (ref "P12") (pin "1") (pinfunction "1_1") (pintype "passive"))
    )
    (net (code "6") (name "/AIN1") (class "Default")
      (node (ref "Q1") (pin "3") (pinfunction "C/A_3") (pintype "power_in"))
      (node (ref "R22") (pin "2") (pinfunction "2_2") (pintype "passive"))
      (node (ref "U11") (pin "14") (pinfunction "PA0/WKUP/USART2_CTS/ADC12_IN0_/TIM2_CH1_ETR_14") (pintype "passive"))
    )
    (net (code "7") (name "/ANI2") (class "Default")
      (node (ref "Q3") (pin "3") (pinfunction "C/A_3") (pintype "power_in"))
      (node (ref "R34") (pin "2") (pinfunction "2_2") (pintype "passive"))
      (node (ref "U11") (pin "15") (pinfunction "PA1/USART2_RTS_/ADC12_IN1/TIM2_CH2_15") (pintype "passive"))
    )
    (net (code "8") (name "/AO-1") (class "Default")
      (node (ref "IC1") (pin "7") (pinfunction "2Out_7") (pintype "passive"))
      (node (ref "P6") (pin "2") (pinfunction "2_2") (pintype "passive"))
      (node (ref "R3") (pin "2") (pinfunction "2_2") (pintype "passive"))
    )
    (net (code "9") (name "/AO-2") (class "Default")
      (node (ref "IC1") (pin "1") (pinfunction "1Out_1") (pintype "passive"))
      (node (ref "P5") (pin "2") (pinfunction "2_2") (pintype "passive"))
      (node (ref "R2") (pin "2") (pinfunction "2_2") (pintype "passive"))
    )
    (net (code "10") (name "/AO1") (class "Default")
      (node (ref "R7") (pin "1") (pinfunction "1_1") (pintype "passive"))
      (node (ref "U11") (pin "10") (pinfunction "PC2/ADC12_IN12_10") (pintype "passive"))
    )
    (net (code "11") (name "/AO2") (class "Default")
      (node (ref "R14") (pin "1") (pinfunction "1_1") (pintype "passive"))
      (node (ref "U11") (pin "11") (pinfunction "PC3/ADC12_IN13_11") (pintype "passive"))
    )
    (net (code "12") (name "/AT_CMD") (class "Default")
      (node (ref "U11") (pin "55") (pinfunction "PB3/JTDO/TRACESWO/TIM2_CH2/SPI1_SCK_55") (pintype "passive"))
      (node (ref "U5") (pin "4") (pinfunction "AT_4") (pintype "passive"))
    )
    (net (code "13") (name "/B") (class "Default")
      (node (ref "F2") (pin "2") (pinfunction "2_2") (pintype "passive"))
      (node (ref "P11") (pin "2") (pinfunction "2_2") (pintype "passive"))
      (node (ref "P12") (pin "2") (pinfunction "2_2") (pintype "passive"))
    )
    (net (code "14") (name "/BOOT0") (class "Default")
      (node (ref "R62") (pin "2") (pinfunction "2_2") (pintype "passive"))
      (node (ref "U11") (pin "60") (pinfunction "BOOT0_60") (pintype "passive"))
    )
    (net (code "15") (name "/BOOT1") (class "Default")
      (node (ref "R61") (pin "1") (pinfunction "1_1") (pintype "passive"))
      (node (ref "U11") (pin "28") (pinfunction "PB2-BOOT1_28") (pintype "passive"))
    )
    (net (code "16") (name "/D+") (class "Default")
      (node (ref "R58") (pin "1") (pinfunction "1_1") (pintype "passive"))
      (node (ref "R59") (pin "1") (pinfunction "1_1") (pintype "passive"))
      (node (ref "U12") (pin "3") (pinfunction "3_3") (pintype "passive"))
    )
    (net (code "17") (name "/D-") (class "Default")
      (node (ref "R56") (pin "1") (pinfunction "1_1") (pintype "passive"))
      (node (ref "U12") (pin "2") (pinfunction "2_2") (pintype "passive"))
    )
    (net (code "18") (name "/DI1") (class "Default")
      (node (ref "R19") (pin "2") (pinfunction "2_2") (pintype "passive"))
      (node (ref "U11") (pin "22") (pinfunction "PA6/SPI1_MISO_/TIM1_BKIN/ADC12_IN6/TIM3_CH1_22") (pintype "passive"))
      (node (ref "U3") (pin "3") (pinfunction "Emitter_3") (pintype "passive"))
    )
    (net (code "19") (name "/DI2") (class "Default")
      (node (ref "R33") (pin "2") (pinfunction "2_2") (pintype "passive"))
      (node (ref "U11") (pin "23") (pinfunction "PA7/SPI1_MISI_/TIM1_CH1N/ADC12_IN7/TIM3_CH2_23") (pintype "passive"))
      (node (ref "U6") (pin "3") (pinfunction "Emitter_3") (pintype "passive"))
    )
    (net (code "20") (name "/DO1") (class "Default")
      (node (ref "R1") (pin "1") (pinfunction "1_1") (pintype "passive"))
      (node (ref "U11") (pin "24") (pinfunction "PC4/ADC12_IN14_24") (pintype "passive"))
    )
    (net (code "21") (name "/DO2") (class "Default")
      (node (ref "R10") (pin "1") (pinfunction "1_1") (pintype "passive"))
      (node (ref "U11") (pin "25") (pinfunction "PC5/ADC12_IN15_25") (pintype "passive"))
    )
    (net (code "22") (name "/EPROM_SCL") (class "Default")
      (node (ref "AT1") (pin "6") (pinfunction "SCL_6") (pintype "passive"))
      (node (ref "R64") (pin "1") (pinfunction "1_1") (pintype "passive"))
      (node (ref "U11") (pin "58") (pinfunction "PB6/USART1_TX/I2C1_SCL_/TIM4_CH1_58") (pintype "passive"))
    )
    (net (code "23") (name "/EPROM_SDA") (class "Default")
      (node (ref "AT1") (pin "5") (pinfunction "SDA_5") (pintype "passive"))
      (node (ref "R65") (pin "1") (pinfunction "1_1") (pintype "passive"))
      (node (ref "U11") (pin "59") (pinfunction "PB7/USART1_RX/I2C1_SDA_/TIM4_CH2_59") (pintype "passive"))
    )
    (net (code "24") (name "/IIN1") (class "Default")
      (node (ref "C13") (pin "2") (pinfunction "2_2") (pintype "passive"))
      (node (ref "P8") (pin "3") (pinfunction "3_3") (pintype "passive"))
      (node (ref "R20") (pin "2") (pinfunction "2_2") (pintype "passive"))
      (node (ref "R22") (pin "1") (pinfunction "1_1") (pintype "passive"))
      (node (ref "R24") (pin "2") (pinfunction "2_2") (pintype "passive"))
    )
    (net (code "25") (name "/IIN2") (class "Default")
      (node (ref "C18") (pin "2") (pinfunction "2_2") (pintype "passive"))
      (node (ref "P10") (pin "3") (pinfunction "3_3") (pintype "passive"))
      (node (ref "R32") (pin "2") (pinfunction "2_2") (pintype "passive"))
      (node (ref "R34") (pin "1") (pinfunction "1_1") (pintype "passive"))
      (node (ref "R36") (pin "2") (pinfunction "2_2") (pintype "passive"))
    )
    (net (code "26") (name "/K1") (class "Default")
      (node (ref "R66") (pin "2") (pinfunction "2_2") (pintype "passive"))
      (node (ref "S2") (pin "1") (pinfunction "1_1") (pintype "passive"))
      (node (ref "U11") (pin "8") (pinfunction "PC0/ADC12_IN10_8") (pintype "passive"))
    )
    (net (code "27") (name "/K2") (class "Default")
      (node (ref "R67") (pin "2") (pinfunction "2_2") (pintype "passive"))
      (node (ref "S3") (pin "1") (pinfunction "1_1") (pintype "passive"))
      (node (ref "U11") (pin "9") (pinfunction "PC1/ADC12_IN11_9") (pintype "passive"))
    )
    (net (code "28") (name "/KCZJ-1") (class "Default")
      (node (ref "U11") (pin "26") (pinfunction "PB0/ADC12_IN8/TIM3_CH3/TIM1_CH2N_26") (pintype "passive"))
      (node (ref "U9") (pin "2") (pinfunction "LED_Cathode_2") (pintype "passive"))
    )
    (net (code "29") (name "/KCZJ-2") (class "Default")
      (node (ref "U10") (pin "2") (pinfunction "LED_Cathode_2") (pintype "passive"))
      (node (ref "U11") (pin "27") (pinfunction "PB1/ADC12_IN9/TIM3_CH4/TIM1_CH3N_27") (pintype "passive"))
    )
    (net (code "30") (name "/LED1") (class "Default")
      (node (ref "R37") (pin "1") (pinfunction "1_1") (pintype "passive"))
      (node (ref "U11") (pin "36") (pinfunction "PB15/SPI2_MOSI/TIM1_CH3N_36") (pintype "passive"))
    )
    (net (code "31") (name "/LED2") (class "Default")
      (node (ref "R49") (pin "2") (pinfunction "2_2") (pintype "passive"))
      (node (ref "U11") (pin "35") (pinfunction "PB14/SPI2_MISO/TIM1_CH2N/USART3_RTS_35") (pintype "passive"))
    )
    (net (code "32") (name "/LED3") (class "Default")
      (node (ref "R52") (pin "1") (pinfunction "1_1") (pintype "passive"))
      (node (ref "U11") (pin "34") (pinfunction "PB13/SPI2_SCK/USART3_CTS/_TIM1_CH1N_34") (pintype "passive"))
    )
    (net (code "33") (name "/LED4") (class "Default")
      (node (ref "R54") (pin "2") (pinfunction "2_2") (pintype "passive"))
      (node (ref "U11") (pin "33") (pinfunction "PB12/SPI2_NSS/I2C2_SMBA/USART3_CK/TIM1_BKIN_33") (pintype "passive"))
    )
    (net (code "34") (name "/LORA_PWR") (class "Default")
      (node (ref "R31") (pin "1") (pinfunction "1_1") (pintype "passive"))
      (node (ref "U11") (pin "56") (pinfunction "PB4/JNTRST/TIM3_CH1/SPI1_MISO_56") (pintype "passive"))
    )
    (net (code "35") (name "/LoRa_RX") (class "Default")
      (node (ref "U11") (pin "29") (pinfunction "PB10/I2C2_SCL/USART3_TX/TIM2_CH3_29") (pintype "passive"))
      (node (ref "U5") (pin "5") (pinfunction "UART_RxD_5") (pintype "passive"))
    )
    (net (code "36") (name "/LoRa_TX") (class "Default")
      (node (ref "U11") (pin "30") (pinfunction "PB11/I2C2_SDA/USART3_RX/TIM2_CH4_30") (pintype "passive"))
      (node (ref "U5") (pin "6") (pinfunction "UART_TxD_6") (pintype "passive"))
    )
    (net (code "37") (name "/MCU_RX") (class "Default")
      (node (ref "U11") (pin "43") (pinfunction "PA10/USART1_RX/TIM1_CH3_43") (pintype "passive"))
      (node (ref "XS2") (pin "2") (pinfunction "2_2") (pintype "passive"))
    )
    (net (code "38") (name "/MCU_TX") (class "Default")
      (node (ref "U11") (pin "42") (pinfunction "PA9/USART1_TX/TIM1_CH2_42") (pintype "passive"))
      (node (ref "XS2") (pin "3") (pinfunction "3_3") (pintype "passive"))
    )
    (net (code "39") (name "/RESET") (class "Default")
      (node (ref "C32") (pin "1") (pinfunction "1_1") (pintype "passive"))
      (node (ref "R57") (pin "1") (pinfunction "1_1") (pintype "passive"))
      (node (ref "S1") (pin "2") (pinfunction "2_2") (pintype "passive"))
      (node (ref "U11") (pin "7") (pinfunction "NRST_7") (pintype "passive"))
      (node (ref "XS3") (pin "2") (pinfunction "2_2") (pintype "passive"))
    )
    (net (code "40") (name "/RESETn") (class "Default")
      (node (ref "R30") (pin "2") (pinfunction "2_2") (pintype "passive"))
      (node (ref "U11") (pin "53") (pinfunction "PC12/USART3_CK_53") (pintype "passive"))
      (node (ref "U5") (pin "8") (pinfunction "RESETn_8") (pintype "passive"))
    )
    (net (code "41") (name "/SWCLK") (class "Default")
      (node (ref "U11") (pin "49") (pinfunction "PA14/JTCK-SWCLK_49") (pintype "passive"))
      (node (ref "XS3") (pin "4") (pinfunction "4_4") (pintype "passive"))
    )
    (net (code "42") (name "/SWDIO") (class "Default")
      (node (ref "U11") (pin "46") (pinfunction "PA13/JTMS-SWDIO_46") (pintype "passive"))
      (node (ref "XS3") (pin "3") (pinfunction "3_3") (pintype "passive"))
    )
    (net (code "43") (name "/USBDM") (class "Default")
      (node (ref "R56") (pin "2") (pinfunction "2_2") (pintype "passive"))
      (node (ref "U11") (pin "44") (pinfunction "PA11/USART1_CTS/USBDM_/CAN_RX_/TIM1_CH4_44") (pintype "passive"))
    )
    (net (code "44") (name "/USBDP") (class "Default")
      (node (ref "R58") (pin "2") (pinfunction "2_2") (pintype "passive"))
      (node (ref "U11") (pin "45") (pinfunction "PA12/USART1_RTS/USBDP/CAN_TX_/TIM1_ETR_45") (pintype "passive"))
    )
    (net (code "45") (name "/VIN1") (class "Default")
      (node (ref "P8") (pin "2") (pinfunction "2_2") (pintype "passive"))
      (node (ref "R20") (pin "1") (pinfunction "1_1") (pintype "passive"))
    )
    (net (code "46") (name "/VIN2") (class "Default")
      (node (ref "P10") (pin "2") (pinfunction "2_2") (pintype "passive"))
      (node (ref "R32") (pin "1") (pinfunction "1_1") (pintype "passive"))
    )
    (net (code "47") (name "/WP") (class "Default")
      (node (ref "AT1") (pin "7") (pinfunction "WP_7") (pintype "passive"))
      (node (ref "R63") (pin "1") (pinfunction "1_1") (pintype "passive"))
      (node (ref "U11") (pin "57") (pinfunction "PB5/TIM3_CH2/SPI1_MOSI_/_I2C1_SMBA_57") (pintype "passive"))
    )
    (net (code "48") (name "/Wake_UP") (class "Default")
      (node (ref "R28") (pin "2") (pinfunction "2_2") (pintype "passive"))
      (node (ref "U11") (pin "54") (pinfunction "PD2/TIM3_ETR_54") (pintype "passive"))
      (node (ref "U5") (pin "7") (pinfunction "Wake_UP_7") (pintype "passive"))
    )
    (net (code "49") (name "3.3V") (class "Default")
      (node (ref "AT1") (pin "8") (pinfunction "VCC_8") (pintype "passive"))
      (node (ref "C19") (pin "1") (pinfunction "1_1") (pintype "passive"))
      (node (ref "C24") (pin "1") (pinfunction "1_1") (pintype "passive"))
      (node (ref "C25") (pin "1") (pinfunction "1_1") (pintype "passive"))
      (node (ref "C26") (pin "1") (pinfunction "1_1") (pintype "passive"))
      (node (ref "C29") (pin "2") (pinfunction "2_2") (pintype "passive"))
      (node (ref "C34") (pin "2") (pinfunction "2_2") (pintype "passive"))
      (node (ref "C35") (pin "2") (pinfunction "2_2") (pintype "passive"))
      (node (ref "C36") (pin "2") (pinfunction "2_2") (pintype "passive"))
      (node (ref "C37") (pin "2") (pinfunction "2_2") (pintype "passive"))
      (node (ref "C38") (pin "2") (pinfunction "2_2") (pintype "passive"))
      (node (ref "C39") (pin "1") (pinfunction "1_1") (pintype "passive"))
      (node (ref "C40") (pin "1") (pinfunction "1_1") (pintype "passive"))
      (node (ref "P15") (pin "1") (pinfunction "1_1") (pintype "passive"))
      (node (ref "P15") (pin "2") (pinfunction "2_2") (pintype "passive"))
      (node (ref "Q1") (pin "2") (pinfunction "CATHODE_2") (pintype "passive"))
      (node (ref "Q3") (pin "2") (pinfunction "CATHODE_2") (pintype "passive"))
      (node (ref "R39") (pin "2") (pinfunction "2_2") (pintype "passive"))
      (node (ref "R40") (pin "2") (pinfunction "2_2") (pintype "passive"))
      (node (ref "R41") (pin "2") (pinfunction "2_2") (pintype "passive"))
      (node (ref "R46") (pin "1") (pinfunction "1_1") (pintype "passive"))
      (node (ref "R47") (pin "1") (pinfunction "1_1") (pintype "passive"))
      (node (ref "R50") (pin "2") (pinfunction "2_2") (pintype "passive"))
      (node (ref "R57") (pin "2") (pinfunction "2_2") (pintype "passive"))
      (node (ref "R59") (pin "2") (pinfunction "2_2") (pintype "passive"))
      (node (ref "R63") (pin "2") (pinfunction "2_2") (pintype "passive"))
      (node (ref "R64") (pin "2") (pinfunction "2_2") (pintype "passive"))
      (node (ref "R65") (pin "2") (pinfunction "2_2") (pintype "passive"))
      (node (ref "R66") (pin "1") (pinfunction "1_1") (pintype "passive"))
      (node (ref "R67") (pin "1") (pinfunction "1_1") (pintype "passive"))
      (node (ref "U11") (pin "13") (pinfunction "VDDA_13") (pintype "passive"))
      (node (ref "U11") (pin "19") (pinfunction "VDD4_19") (pintype "passive"))
      (node (ref "U11") (pin "32") (pinfunction "VDD1_32") (pintype "passive"))
      (node (ref "U11") (pin "48") (pinfunction "VDD2_48") (pintype "passive"))
      (node (ref "U11") (pin "64") (pinfunction "VDD3_64") (pintype "passive"))
      (node (ref "U3") (pin "4") (pinfunction "Collector_4") (pintype "passive"))
      (node (ref "U6") (pin "4") (pinfunction "Collector_4") (pintype "passive"))
      (node (ref "U7") (pin "14") (pinfunction "VCC_14") (pintype "passive"))
      (node (ref "U8") (pin "8") (pinfunction "VCC_8") (pintype "power_in"))
      (node (ref "XS2") (pin "1") (pinfunction "1_1") (pintype "passive"))
      (node (ref "XS3") (pin "5") (pinfunction "5_5") (pintype "passive"))
    )
    (net (code "50") (name "24V") (class "Default")
      (node (ref "C4") (pin "1") (pinfunction "1_1") (pintype "passive"))
      (node (ref "LM1") (pin "1") (pinfunction "VIN_1") (pintype "passive"))
      (node (ref "P10") (pin "1") (pinfunction "1_1") (pintype "passive"))
      (node (ref "P2") (pin "2") (pinfunction "2_2") (pintype "passive"))
      (node (ref "P7") (pin "3") (pinfunction "3_3") (pintype "passive"))
      (node (ref "P8") (pin "1") (pinfunction "1_1") (pintype "passive"))
      (node (ref "P9") (pin "3") (pinfunction "3_3") (pintype "passive"))
      (node (ref "RL1") (pin "6") (pinfunction "6_6") (pintype "passive"))
      (node (ref "RL2") (pin "6") (pinfunction "6_6") (pintype "passive"))
      (node (ref "U1") (pin "4") (pinfunction "Collector_4") (pintype "passive"))
      (node (ref "U2") (pin "4") (pinfunction "Collector_4") (pintype "passive"))
    )
    (net (code "51") (name "COM+1") (class "Default")
      (node (ref "P13") (pin "1") (pinfunction "1_1") (pintype "passive"))
      (node (ref "RL1") (pin "3") (pinfunction "3_3") (pintype "passive"))
      (node (ref "RL1") (pin "4") (pinfunction "4_4") (pintype "passive"))
    )
    (net (code "52") (name "COM+2") (class "Default")
      (node (ref "P14") (pin "1") (pinfunction "1_1") (pintype "passive"))
      (node (ref "RL2") (pin "3") (pinfunction "3_3") (pintype "passive"))
      (node (ref "RL2") (pin "4") (pinfunction "4_4") (pintype "passive"))
    )
    (net (code "53") (name "GND") (class "Default")
      (node (ref "AT1") (pin "1") (pinfunction "A0_1") (pintype "passive"))
      (node (ref "AT1") (pin "2") (pinfunction "A1_2") (pintype "passive"))
      (node (ref "AT1") (pin "3") (pinfunction "A2_3") (pintype "passive"))
      (node (ref "AT1") (pin "4") (pinfunction "GND_4") (pintype "passive"))
      (node (ref "C1") (pin "1") (pinfunction "1_1") (pintype "passive"))
      (node (ref "C10") (pin "2") (pinfunction "2_2") (pintype "passive"))
      (node (ref "C11") (pin "1") (pinfunction "1_1") (pintype "passive"))
      (node (ref "C12") (pin "1") (pinfunction "1_1") (pintype "passive"))
      (node (ref "C13") (pin "1") (pinfunction "1_1") (pintype "passive"))
      (node (ref "C14") (pin "1") (pinfunction "1_1") (pintype "passive"))
      (node (ref "C15") (pin "1") (pinfunction "1_1") (pintype "passive"))
      (node (ref "C16") (pin "1") (pinfunction "1_1") (pintype "passive"))
      (node (ref "C17") (pin "1") (pinfunction "1_1") (pintype "passive"))
      (node (ref "C18") (pin "1") (pinfunction "1_1") (pintype "passive"))
      (node (ref "C19") (pin "2") (pinfunction "2_2") (pintype "passive"))
      (node (ref "C2") (pin "1") (pinfunction "1_1") (pintype "passive"))
      (node (ref "C20") (pin "2") (pinfunction "2_2") (pintype "passive"))
      (node (ref "C21") (pin "1") (pinfunction "1_1") (pintype "passive"))
      (node (ref "C22") (pin "1") (pinfunction "1_1") (pintype "passive"))
      (node (ref "C23") (pin "1") (pinfunction "1_1") (pintype "passive"))
      (node (ref "C24") (pin "2") (pinfunction "2_2") (pintype "passive"))
      (node (ref "C25") (pin "2") (pinfunction "2_2") (pintype "passive"))
      (node (ref "C26") (pin "2") (pinfunction "2_2") (pintype "passive"))
      (node (ref "C27") (pin "2") (pinfunction "2_2") (pintype "passive"))
      (node (ref "C28") (pin "2") (pinfunction "2_2") (pintype "passive"))
      (node (ref "C29") (pin "1") (pinfunction "1_1") (pintype "passive"))
      (node (ref "C3") (pin "2") (pinfunction "2_2") (pintype "passive"))
      (node (ref "C30") (pin "2") (pinfunction "2_2") (pintype "passive"))
      (node (ref "C31") (pin "2") (pinfunction "2_2") (pintype "passive"))
      (node (ref "C32") (pin "2") (pinfunction "2_2") (pintype "passive"))
      (node (ref "C33") (pin "1") (pinfunction "1_1") (pintype "passive"))
      (node (ref "C34") (pin "1") (pinfunction "1_1") (pintype "passive"))
      (node (ref "C35") (pin "1") (pinfunction "1_1") (pintype "passive"))
      (node (ref "C36") (pin "1") (pinfunction "1_1") (pintype "passive"))
      (node (ref "C37") (pin "1") (pinfunction "1_1") (pintype "passive"))
      (node (ref "C38") (pin "1") (pinfunction "1_1") (pintype "passive"))
      (node (ref "C39") (pin "2") (pinfunction "2_2") (pintype "passive"))
      (node (ref "C4") (pin "2") (pinfunction "2_2") (pintype "passive"))
      (node (ref "C40") (pin "2") (pinfunction "2_2") (pintype "passive"))
      (node (ref "C5") (pin "1") (pinfunction "1_1") (pintype "passive"))
      (node (ref "C6") (pin "1") (pinfunction "1_1") (pintype "passive"))
      (node (ref "C7") (pin "1") (pinfunction "1_1") (pintype "passive"))
      (node (ref "C8") (pin "1") (pinfunction "1_1") (pintype "passive"))
      (node (ref "C9") (pin "1") (pinfunction "1_1") (pintype "passive"))
      (node (ref "D1") (pin "1") (pinfunction "A_1") (pintype "passive"))
      (node (ref "D12") (pin "K") (pinfunction "K_K") (pintype "passive"))
      (node (ref "D13") (pin "K") (pinfunction "K_K") (pintype "passive"))
      (node (ref "D2") (pin "1") (pinfunction "A_1") (pintype "passive"))
      (node (ref "D3") (pin "1") (pinfunction "A_1") (pintype "passive"))
      (node (ref "D4") (pin "1") (pinfunction "A_1") (pintype "passive"))
      (node (ref "D5") (pin "K") (pinfunction "K_K") (pintype "passive"))
      (node (ref "D6") (pin "K") (pinfunction "K_K") (pintype "passive"))
      (node (ref "D7") (pin "1") (pinfunction "A_1") (pintype "passive"))
      (node (ref "GND-1") (pin "1") (pinfunction "1_1") (pintype "passive"))
      (node (ref "GND1") (pin "1") (pinfunction "1_1") (pintype "passive"))
      (node (ref "IC1") (pin "4") (pinfunction "GND_4") (pintype "passive"))
      (node (ref "IC2") (pin "2") (pinfunction "GND_2") (pintype "passive"))
      (node (ref "LED1") (pin "2") (pinfunction "2_2") (pintype "passive"))
      (node (ref "LM1") (pin "3") (pinfunction "GND_3") (pintype "passive"))
      (node (ref "LM1") (pin "5") (pinfunction "ON/OFF_5") (pintype "passive"))
      (node (ref "P1") (pin "2") (pinfunction "2_2") (pintype "passive"))
      (node (ref "P10") (pin "4") (pinfunction "4_4") (pintype "passive"))
      (node (ref "P13") (pin "2") (pinfunction "2_2") (pintype "passive"))
      (node (ref "P14") (pin "2") (pinfunction "2_2") (pintype "passive"))
      (node (ref "P15") (pin "5") (pinfunction "5_5") (pintype "passive"))
      (node (ref "P15") (pin "6") (pinfunction "6_6") (pintype "passive"))
      (node (ref "P3") (pin "2") (pinfunction "2_2") (pintype "passive"))
      (node (ref "P4") (pin "2") (pinfunction "2_2") (pintype "passive"))
      (node (ref "P5") (pin "1") (pinfunction "1_1") (pintype "passive"))
      (node (ref "P6") (pin "1") (pinfunction "1_1") (pintype "passive"))
      (node (ref "P7") (pin "1") (pinfunction "1_1") (pintype "passive"))
      (node (ref "P8") (pin "4") (pinfunction "4_4") (pintype "passive"))
      (node (ref "P9") (pin "1") (pinfunction "1_1") (pintype "passive"))
      (node (ref "Q1") (pin "1") (pinfunction "ANODE_1") (pintype "passive"))
      (node (ref "Q3") (pin "1") (pinfunction "ANODE_1") (pintype "passive"))
      (node (ref "Q4") (pin "2") (pinfunction "E_2") (pintype "passive"))
      (node (ref "R16") (pin "1") (pinfunction "1_1") (pintype "passive"))
      (node (ref "R19") (pin "1") (pinfunction "1_1") (pintype "passive"))
      (node (ref "R24") (pin "1") (pinfunction "1_1") (pintype "passive"))
      (node (ref "R28") (pin "1") (pinfunction "1_1") (pintype "passive"))
      (node (ref "R29") (pin "1") (pinfunction "1_1") (pintype "passive"))
      (node (ref "R33") (pin "1") (pinfunction "1_1") (pintype "passive"))
      (node (ref "R35") (pin "1") (pinfunction "1_1") (pintype "passive"))
      (node (ref "R36") (pin "1") (pinfunction "1_1") (pintype "passive"))
      (node (ref "R38") (pin "1") (pinfunction "1_1") (pintype "passive"))
      (node (ref "R43") (pin "1") (pinfunction "1_1") (pintype "passive"))
      (node (ref "R53") (pin "1") (pinfunction "1_1") (pintype "passive"))
      (node (ref "R60") (pin "1") (pinfunction "1_1") (pintype "passive"))
      (node (ref "RL1") (pin "1") (pinfunction "1_1") (pintype "passive"))
      (node (ref "RL2") (pin "1") (pinfunction "1_1") (pintype "passive"))
      (node (ref "S1") (pin "1") (pinfunction "1_1") (pintype "passive"))
      (node (ref "S2") (pin "2") (pinfunction "2_2") (pintype "passive"))
      (node (ref "S3") (pin "2") (pinfunction "2_2") (pintype "passive"))
      (node (ref "U1") (pin "2") (pinfunction "LED_Cathode_2") (pintype "passive"))
      (node (ref "U10") (pin "3") (pinfunction "Emitter_3") (pintype "passive"))
      (node (ref "U11") (pin "12") (pinfunction "VSSA_12") (pintype "passive"))
      (node (ref "U11") (pin "18") (pinfunction "VSS4_18") (pintype "passive"))
      (node (ref "U11") (pin "31") (pinfunction "VSS1_31") (pintype "passive"))
      (node (ref "U11") (pin "47") (pinfunction "VSS2_47") (pintype "passive"))
      (node (ref "U11") (pin "63") (pinfunction "VSS3_63") (pintype "passive"))
      (node (ref "U12") (pin "4") (pinfunction "4_4") (pintype "passive"))
      (node (ref "U2") (pin "2") (pinfunction "LED_Cathode_2") (pintype "passive"))
      (node (ref "U3") (pin "2") (pinfunction "LED_Cathode_2") (pintype "passive"))
      (node (ref "U4") (pin "2") (pinfunction "GND_2") (pintype "passive"))
      (node (ref "U5") (pin "9") (pinfunction "GND_9") (pintype "passive"))
      (node (ref "U6") (pin "2") (pinfunction "LED_Cathode_2") (pintype "passive"))
      (node (ref "U7") (pin "7") (pinfunction "GND_7") (pintype "passive"))
      (node (ref "U8") (pin "5") (pinfunction "GND_5") (pintype "power_in"))
      (node (ref "U9") (pin "3") (pinfunction "Emitter_3") (pintype "passive"))
      (node (ref "V1") (pin "2") (pinfunction "E_2") (pintype "passive"))
      (node (ref "V2") (pin "2") (pinfunction "E_2") (pintype "passive"))
      (node (ref "XS1") (pin "1") (pinfunction "1_1") (pintype "passive"))
      (node (ref "XS2") (pin "4") (pinfunction "4_4") (pintype "passive"))
      (node (ref "XS3") (pin "1") (pinfunction "1_1") (pintype "passive"))
      (node (ref "Y2") (pin "2") (pinfunction "G_2") (pintype "passive"))
      (node (ref "Y2") (pin "4") (pinfunction "G_4") (pintype "passive"))
    )
    (net (code "54") (name "GROUND") (class "Default")
      (node (ref "D14") (pin "1") (pinfunction "A_1") (pintype "passive"))
      (node (ref "D8") (pin "2") (pinfunction "K_2") (pintype "passive"))
      (node (ref "GROUND1") (pin "1") (pinfunction "1_1") (pintype "passive"))
    )
    (net (code "55") (name "LoRa_3V3") (class "Default")
      (node (ref "C16") (pin "2") (pinfunction "2_2") (pintype "passive"))
      (node (ref "C17") (pin "2") (pinfunction "2_2") (pintype "passive"))
      (node (ref "R18") (pin "2") (pinfunction "2_2") (pintype "passive"))
      (node (ref "R30") (pin "1") (pinfunction "1_1") (pintype "passive"))
      (node (ref "U5") (pin "10") (pinfunction "VCC_10") (pintype "passive"))
    )
    (net (code "56") (name "Net-(C1-Pad2)") (class "Default")
      (node (ref "C1") (pin "2") (pinfunction "2_2") (pintype "passive"))
      (node (ref "R5") (pin "1") (pinfunction "1_1") (pintype "passive"))
      (node (ref "R6") (pin "2") (pinfunction "2_2") (pintype "passive"))
    )
    (net (code "57") (name "Net-(C7-Pad2)") (class "Default")
      (node (ref "C7") (pin "2") (pinfunction "2_2") (pintype "passive"))
      (node (ref "R12") (pin "1") (pinfunction "1_1") (pintype "passive"))
      (node (ref "R13") (pin "2") (pinfunction "2_2") (pintype "passive"))
    )
    (net (code "58") (name "Net-(C33-Pad2)") (class "Default")
      (node (ref "C33") (pin "2") (pinfunction "2_2") (pintype "passive"))
      (node (ref "R60") (pin "2") (pinfunction "2_2") (pintype "passive"))
      (node (ref "U12") (pin "5") (pinfunction "5_5") (pintype "passive"))
    )
    (net (code "59") (name "Net-(D1-K)") (class "Default")
      (node (ref "D1") (pin "2") (pinfunction "K_2") (pintype "passive"))
      (node (ref "R1") (pin "2") (pinfunction "2_2") (pintype "passive"))
      (node (ref "U1") (pin "1") (pinfunction "LED_Anode_1") (pintype "passive"))
    )
    (net (code "60") (name "Net-(D2-K)") (class "Default")
      (node (ref "D2") (pin "2") (pinfunction "K_2") (pintype "passive"))
      (node (ref "L1") (pin "1") (pinfunction "1_1") (pintype "passive"))
      (node (ref "LM1") (pin "2") (pinfunction "OUTPUT_2") (pintype "passive"))
    )
    (net (code "61") (name "Net-(D3-K)") (class "Default")
      (node (ref "D3") (pin "2") (pinfunction "K_2") (pintype "passive"))
      (node (ref "R10") (pin "2") (pinfunction "2_2") (pintype "passive"))
      (node (ref "U2") (pin "1") (pinfunction "LED_Anode_1") (pintype "passive"))
    )
    (net (code "62") (name "Net-(D4-K)") (class "Default")
      (node (ref "C9") (pin "2") (pinfunction "2_2") (pintype "passive"))
      (node (ref "D4") (pin "2") (pinfunction "K_2") (pintype "passive"))
      (node (ref "R15") (pin "2") (pinfunction "2_2") (pintype "passive"))
      (node (ref "R16") (pin "2") (pinfunction "2_2") (pintype "passive"))
      (node (ref "U3") (pin "1") (pinfunction "LED_Anode_1") (pintype "passive"))
    )
    (net (code "63") (name "Net-(D5-PadA)") (class "Default")
      (node (ref "D5") (pin "A") (pinfunction "A_A") (pintype "passive"))
      (node (ref "R23") (pin "1") (pinfunction "1_1") (pintype "passive"))
    )
    (net (code "64") (name "Net-(D6-PadA)") (class "Default")
      (node (ref "D6") (pin "A") (pinfunction "A_A") (pintype "passive"))
      (node (ref "R25") (pin "1") (pinfunction "1_1") (pintype "passive"))
    )
    (net (code "65") (name "Net-(D7-K)") (class "Default")
      (node (ref "C15") (pin "2") (pinfunction "2_2") (pintype "passive"))
      (node (ref "D7") (pin "2") (pinfunction "K_2") (pintype "passive"))
      (node (ref "R26") (pin "2") (pinfunction "2_2") (pintype "passive"))
      (node (ref "R29") (pin "2") (pinfunction "2_2") (pintype "passive"))
      (node (ref "U6") (pin "1") (pinfunction "LED_Anode_1") (pintype "passive"))
    )
    (net (code "66") (name "Net-(D8-A)") (class "Default")
      (node (ref "D8") (pin "1") (pinfunction "A_1") (pintype "passive"))
      (node (ref "D9") (pin "1") (pinfunction "A_1") (pintype "passive"))
      (node (ref "F2") (pin "1") (pinfunction "1_1") (pintype "passive"))
      (node (ref "R38") (pin "2") (pinfunction "2_2") (pintype "passive"))
      (node (ref "U8") (pin "7") (pinfunction "B_7") (pintype "power_in"))
    )
    (net (code "67") (name "Net-(D11-A)") (class "Default")
      (node (ref "D11") (pin "1") (pinfunction "A_1") (pintype "passive"))
      (node (ref "LED3") (pin "2") (pinfunction "2_2") (pintype "passive"))
      (node (ref "RL1") (pin "5") (pinfunction "5_5") (pintype "passive"))
      (node (ref "U9") (pin "4") (pinfunction "Collector_4") (pintype "passive"))
    )
    (net (code "68") (name "Net-(D12-PadA)") (class "Default")
      (node (ref "D12") (pin "A") (pinfunction "A_A") (pintype "passive"))
      (node (ref "R42") (pin "1") (pinfunction "1_1") (pintype "passive"))
    )
    (net (code "69") (name "Net-(D13-PadA)") (class "Default")
      (node (ref "D13") (pin "A") (pinfunction "A_A") (pintype "passive"))
      (node (ref "R44") (pin "1") (pinfunction "1_1") (pintype "passive"))
    )
    (net (code "70") (name "Net-(D14-K)") (class "Default")
      (node (ref "D14") (pin "2") (pinfunction "K_2") (pintype "passive"))
      (node (ref "D9") (pin "2") (pinfunction "K_2") (pintype "passive"))
      (node (ref "F3") (pin "1") (pinfunction "1_1") (pintype "passive"))
      (node (ref "R47") (pin "2") (pinfunction "2_2") (pintype "passive"))
      (node (ref "U8") (pin "6") (pinfunction "A_6") (pintype "power_in"))
    )
    (net (code "71") (name "Net-(D15-A)") (class "Default")
      (node (ref "D15") (pin "1") (pinfunction "A_1") (pintype "passive"))
      (node (ref "LED4") (pin "2") (pinfunction "2_2") (pintype "passive"))
      (node (ref "RL2") (pin "5") (pinfunction "5_5") (pintype "passive"))
      (node (ref "U10") (pin "4") (pinfunction "Collector_4") (pintype "passive"))
    )
    (net (code "72") (name "Net-(F1-Pad1)") (class "Default")
      (node (ref "F1") (pin "1") (pinfunction "1_1") (pintype "passive"))
      (node (ref "P3") (pin "1") (pinfunction "1_1") (pintype "passive"))
    )
    (net (code "73") (name "Net-(F1-Pad2)") (class "Default")
      (node (ref "F1") (pin "2") (pinfunction "2_2") (pintype "passive"))
      (node (ref "P2") (pin "1") (pinfunction "1_1") (pintype "passive"))
    )
    (net (code "74") (name "Net-(F4-Pad1)") (class "Default")
      (node (ref "F4") (pin "1") (pinfunction "1_1") (pintype "passive"))
      (node (ref "U12") (pin "1") (pinfunction "1_1") (pintype "passive"))
    )
    (net (code "75") (name "Net-(IC1-1IN+)") (class "Default")
      (node (ref "C2") (pin "2") (pinfunction "2_2") (pintype "passive"))
      (node (ref "IC1") (pin "3") (pinfunction "1IN+_3") (pintype "passive"))
      (node (ref "R5") (pin "2") (pinfunction "2_2") (pintype "passive"))
    )
    (net (code "76") (name "Net-(IC1-1IN-)") (class "Default")
      (node (ref "IC1") (pin "2") (pinfunction "1IN-_2") (pintype "passive"))
      (node (ref "R2") (pin "1") (pinfunction "1_1") (pintype "passive"))
    )
    (net (code "77") (name "Net-(IC1-2IN+)") (class "Default")
      (node (ref "C8") (pin "2") (pinfunction "2_2") (pintype "passive"))
      (node (ref "IC1") (pin "5") (pinfunction "2IN+_5") (pintype "passive"))
      (node (ref "R12") (pin "2") (pinfunction "2_2") (pintype "passive"))
    )
    (net (code "78") (name "Net-(IC1-2IN-)") (class "Default")
      (node (ref "IC1") (pin "6") (pinfunction "2IN-_6") (pintype "passive"))
      (node (ref "R3") (pin "1") (pinfunction "1_1") (pintype "passive"))
    )
    (net (code "79") (name "Net-(IC2-BYP)") (class "Default")
      (node (ref "C23") (pin "2") (pinfunction "2_2") (pintype "passive"))
      (node (ref "IC2") (pin "4") (pinfunction "BYP_4") (pintype "passive"))
    )
    (net (code "80") (name "Net-(IC2-VOUT)") (class "Default")
      (node (ref "5V") (pin "1") (pinfunction "1_1") (pintype "passive"))
      (node (ref "C21") (pin "2") (pinfunction "2_2") (pintype "passive"))
      (node (ref "IC2") (pin "5") (pinfunction "VOUT_5") (pintype "passive"))
      (node (ref "R41") (pin "1") (pinfunction "1_1") (pintype "passive"))
    )
    (net (code "81") (name "Net-(LED1-Pad1)") (class "Default")
      (node (ref "LED1") (pin "1") (pinfunction "1_1") (pintype "passive"))
      (node (ref "R9") (pin "2") (pinfunction "2_2") (pintype "passive"))
    )
    (net (code "82") (name "Net-(LED2-K)") (class "Default")
      (node (ref "LED2") (pin "2") (pinfunction "K_2") (pintype "passive"))
      (node (ref "R43") (pin "2") (pinfunction "2_2") (pintype "passive"))
    )
    (net (code "83") (name "Net-(LED3-Pad1)") (class "Default")
      (node (ref "LED3") (pin "1") (pinfunction "1_1") (pintype "passive"))
      (node (ref "R48") (pin "2") (pinfunction "2_2") (pintype "passive"))
    )
    (net (code "84") (name "Net-(LED4-Pad1)") (class "Default")
      (node (ref "LED4") (pin "1") (pinfunction "1_1") (pintype "passive"))
      (node (ref "R51") (pin "2") (pinfunction "2_2") (pintype "passive"))
    )
    (net (code "85") (name "Net-(LED5-K)") (class "Default")
      (node (ref "LED5") (pin "2") (pinfunction "K_2") (pintype "passive"))
      (node (ref "R53") (pin "2") (pinfunction "2_2") (pintype "passive"))
    )
    (net (code "86") (name "Net-(LM1-FEEDBACK)") (class "Default")
      (node (ref "+1") (pin "1") (pinfunction "1_1") (pintype "passive"))
      (node (ref "C3") (pin "1") (pinfunction "1_1") (pintype "passive"))
      (node (ref "C5") (pin "2") (pinfunction "2_2") (pintype "passive"))
      (node (ref "C6") (pin "2") (pinfunction "2_2") (pintype "passive"))
      (node (ref "L1") (pin "2") (pinfunction "2_2") (pintype "passive"))
      (node (ref "LM1") (pin "4") (pinfunction "FEEDBACK_4") (pintype "passive"))
      (node (ref "R8") (pin "1") (pinfunction "1_1") (pintype "passive"))
    )
    (net (code "87") (name "Net-(P7-Pad2)") (class "Default")
      (node (ref "P7") (pin "2") (pinfunction "2_2") (pintype "passive"))
      (node (ref "R15") (pin "1") (pinfunction "1_1") (pintype "passive"))
    )
    (net (code "88") (name "Net-(P9-Pad2)") (class "Default")
      (node (ref "P9") (pin "2") (pinfunction "2_2") (pintype "passive"))
      (node (ref "R26") (pin "1") (pinfunction "1_1") (pintype "passive"))
    )
    (net (code "89") (name "Net-(P15-Pad3)") (class "Default")
      (node (ref "P15") (pin "3") (pinfunction "3_3") (pintype "passive"))
      (node (ref "R61") (pin "2") (pinfunction "2_2") (pintype "passive"))
    )
    (net (code "90") (name "Net-(P15-Pad4)") (class "Default")
      (node (ref "P15") (pin "4") (pinfunction "4_4") (pintype "passive"))
      (node (ref "R62") (pin "1") (pinfunction "1_1") (pintype "passive"))
    )
    (net (code "91") (name "Net-(Q2-D)") (class "Default")
      (node (ref "Q2") (pin "3") (pinfunction "D_3") (pintype "passive"))
      (node (ref "R17") (pin "1") (pinfunction "1_1") (pintype "passive"))
    )
    (net (code "92") (name "Net-(Q2-G)") (class "Default")
      (node (ref "Q2") (pin "1") (pinfunction "G_1") (pintype "passive"))
      (node (ref "Q4") (pin "3") (pinfunction "C_3") (pintype "passive"))
      (node (ref "R27") (pin "1") (pinfunction "1_1") (pintype "passive"))
    )
    (net (code "93") (name "Net-(Q4-B)") (class "Default")
      (node (ref "Q4") (pin "1") (pinfunction "B_1") (pintype "passive"))
      (node (ref "R31") (pin "2") (pinfunction "2_2") (pintype "passive"))
      (node (ref "R35") (pin "2") (pinfunction "2_2") (pintype "passive"))
    )
    (net (code "94") (name "Net-(Q5-B)") (class "Default")
      (node (ref "Q5") (pin "1") (pinfunction "B_1") (pintype "passive"))
      (node (ref "R37") (pin "2") (pinfunction "2_2") (pintype "passive"))
    )
    (net (code "95") (name "Net-(Q5-E)") (class "Default")
      (node (ref "LED2") (pin "1") (pinfunction "A_1") (pintype "passive"))
      (node (ref "Q5") (pin "2") (pinfunction "E_2") (pintype "passive"))
    )
    (net (code "96") (name "Net-(Q6-B)") (class "Default")
      (node (ref "Q6") (pin "1") (pinfunction "B_1") (pintype "passive"))
      (node (ref "R49") (pin "1") (pinfunction "1_1") (pintype "passive"))
    )
    (net (code "97") (name "Net-(Q6-E)") (class "Default")
      (node (ref "LED2") (pin "3") (pinfunction "A_3") (pintype "passive"))
      (node (ref "Q6") (pin "2") (pinfunction "E_2") (pintype "passive"))
    )
    (net (code "98") (name "Net-(Q7-B)") (class "Default")
      (node (ref "Q7") (pin "1") (pinfunction "B_1") (pintype "passive"))
      (node (ref "R52") (pin "2") (pinfunction "2_2") (pintype "passive"))
    )
    (net (code "99") (name "Net-(Q7-E)") (class "Default")
      (node (ref "LED5") (pin "1") (pinfunction "A_1") (pintype "passive"))
      (node (ref "Q7") (pin "2") (pinfunction "E_2") (pintype "passive"))
    )
    (net (code "100") (name "Net-(Q8-B)") (class "Default")
      (node (ref "Q8") (pin "1") (pinfunction "B_1") (pintype "passive"))
      (node (ref "R54") (pin "1") (pinfunction "1_1") (pintype "passive"))
    )
    (net (code "101") (name "Net-(Q8-E)") (class "Default")
      (node (ref "LED5") (pin "3") (pinfunction "A_3") (pintype "passive"))
      (node (ref "Q8") (pin "2") (pinfunction "E_2") (pintype "passive"))
    )
    (net (code "102") (name "Net-(R55-Pad1)") (class "Default")
      (node (ref "R55") (pin "1") (pinfunction "1_1") (pintype "passive"))
      (node (ref "XS1") (pin "2") (pinfunction "2_2") (pintype "passive"))
    )
    (net (code "103") (name "Net-(U1-Emitter)") (class "Default")
      (node (ref "P1") (pin "1") (pinfunction "1_1") (pintype "passive"))
      (node (ref "U1") (pin "3") (pinfunction "Emitter_3") (pintype "passive"))
    )
    (net (code "104") (name "Net-(U2-Emitter)") (class "Default")
      (node (ref "P4") (pin "1") (pinfunction "1_1") (pintype "passive"))
      (node (ref "U2") (pin "3") (pinfunction "Emitter_3") (pintype "passive"))
    )
    (net (code "105") (name "Net-(U4-BYP)") (class "Default")
      (node (ref "C12") (pin "2") (pinfunction "2_2") (pintype "passive"))
      (node (ref "U4") (pin "4") (pinfunction "BYP_4") (pintype "passive"))
    )
    (net (code "106") (name "Net-(U4-EN)") (class "Default")
      (node (ref "R21") (pin "2") (pinfunction "2_2") (pintype "passive"))
      (node (ref "U4") (pin "3") (pinfunction "EN_3") (pintype "passive"))
    )
    (net (code "107") (name "Net-(U4-VIN)") (class "Default")
      (node (ref "C10") (pin "1") (pinfunction "1_1") (pintype "passive"))
      (node (ref "C14") (pin "2") (pinfunction "2_2") (pintype "passive"))
      (node (ref "R17") (pin "2") (pinfunction "2_2") (pintype "passive"))
      (node (ref "R21") (pin "1") (pinfunction "1_1") (pintype "passive"))
      (node (ref "U4") (pin "1") (pinfunction "VIN_1") (pintype "passive"))
    )
    (net (code "108") (name "Net-(U4-VOUT)") (class "Default")
      (node (ref "C11") (pin "2") (pinfunction "2_2") (pintype "passive"))
      (node (ref "LoRa-1") (pin "1") (pinfunction "1_1") (pintype "passive"))
      (node (ref "R18") (pin "1") (pinfunction "1_1") (pintype "passive"))
      (node (ref "U4") (pin "5") (pinfunction "VOUT_5") (pintype "passive"))
    )
    (net (code "109") (name "Net-(U5-GPIO1)") (class "Default")
      (node (ref "R23") (pin "2") (pinfunction "2_2") (pintype "passive"))
      (node (ref "U5") (pin "1") (pinfunction "GPIO1_1") (pintype "passive"))
    )
    (net (code "110") (name "Net-(U5-GPIO2)") (class "Default")
      (node (ref "R25") (pin "2") (pinfunction "2_2") (pintype "passive"))
      (node (ref "U5") (pin "2") (pinfunction "GPIO2_2") (pintype "passive"))
    )
    (net (code "111") (name "Net-(U7-3Y)") (class "Default")
      (node (ref "R44") (pin "2") (pinfunction "2_2") (pintype "passive"))
      (node (ref "U7") (pin "6") (pinfunction "3Y_6") (pintype "passive"))
    )
    (net (code "112") (name "Net-(U7-4Y)") (class "Default")
      (node (ref "R46") (pin "2") (pinfunction "2_2") (pintype "passive"))
      (node (ref "U7") (pin "9") (pinfunction "4Y_9") (pintype "passive"))
      (node (ref "U8") (pin "1") (pinfunction "RO_1") (pintype "power_in"))
    )
    (net (code "113") (name "Net-(U7-5A)") (class "Default")
      (node (ref "D10") (pin "2") (pinfunction "1_2") (pintype "passive"))
      (node (ref "R45") (pin "1") (pinfunction "1_1") (pintype "passive"))
      (node (ref "U7") (pin "10") (pinfunction "5A_10") (pintype "passive"))
      (node (ref "U8") (pin "4") (pinfunction "DI_4") (pintype "power_in"))
    )
    (net (code "114") (name "Net-(U7-6A)") (class "Default")
      (node (ref "U7") (pin "12") (pinfunction "6A_12") (pintype "passive"))
      (node (ref "U8") (pin "2") (pinfunction "~{RE}_2") (pintype "power_in"))
      (node (ref "U8") (pin "3") (pinfunction "DE_3") (pintype "power_in"))
    )
    (net (code "115") (name "Net-(U7-6Y)") (class "Default")
      (node (ref "C20") (pin "1") (pinfunction "1_1") (pintype "passive"))
      (node (ref "D10") (pin "1") (pinfunction "1_1") (pintype "passive"))
      (node (ref "R45") (pin "2") (pinfunction "2_2") (pintype "passive"))
      (node (ref "U7") (pin "13") (pinfunction "6Y_13") (pintype "passive"))
    )
    (net (code "116") (name "Net-(U9-LED_Anode)") (class "Default")
      (node (ref "R40") (pin "1") (pinfunction "1_1") (pintype "passive"))
      (node (ref "U9") (pin "1") (pinfunction "LED_Anode_1") (pintype "passive"))
    )
    (net (code "117") (name "Net-(U10-LED_Anode)") (class "Default")
      (node (ref "R50") (pin "1") (pinfunction "1_1") (pintype "passive"))
      (node (ref "U10") (pin "1") (pinfunction "LED_Anode_1") (pintype "passive"))
    )
    (net (code "118") (name "Net-(U11-PC14{slash}OSC32_IN)") (class "Default")
      (node (ref "C28") (pin "1") (pinfunction "1_1") (pintype "passive"))
      (node (ref "U11") (pin "3") (pinfunction "PC14/OSC32_IN_3") (pintype "passive"))
      (node (ref "Y1") (pin "2") (pinfunction "2_2") (pintype "passive"))
    )
    (net (code "119") (name "Net-(U11-PC15{slash}OSC32_OUT)") (class "Default")
      (node (ref "C27") (pin "1") (pinfunction "1_1") (pintype "passive"))
      (node (ref "U11") (pin "4") (pinfunction "PC15/OSC32_OUT_4") (pintype "passive"))
      (node (ref "Y1") (pin "1") (pinfunction "1_1") (pintype "passive"))
    )
    (net (code "120") (name "Net-(U11-PD0{slash}OSC_IN)") (class "Default")
      (node (ref "C31") (pin "1") (pinfunction "1_1") (pintype "passive"))
      (node (ref "U11") (pin "5") (pinfunction "PD0/OSC_IN_5") (pintype "passive"))
      (node (ref "Y2") (pin "3") (pinfunction "T2_3") (pintype "passive"))
    )
    (net (code "121") (name "Net-(U11-PD1{slash}OSC_OUT)") (class "Default")
      (node (ref "C30") (pin "1") (pinfunction "1_1") (pintype "passive"))
      (node (ref "U11") (pin "6") (pinfunction "PD1/OSC_OUT_6") (pintype "passive"))
      (node (ref "Y2") (pin "1") (pinfunction "T1_1") (pintype "passive"))
    )
    (net (code "122") (name "Net-(V1-B)") (class "Default")
      (node (ref "R7") (pin "2") (pinfunction "2_2") (pintype "passive"))
      (node (ref "V1") (pin "1") (pinfunction "B_1") (pintype "passive"))
    )
    (net (code "123") (name "Net-(V1-C)") (class "Default")
      (node (ref "R4") (pin "1") (pinfunction "1_1") (pintype "passive"))
      (node (ref "R6") (pin "1") (pinfunction "1_1") (pintype "passive"))
      (node (ref "V1") (pin "3") (pinfunction "C_3") (pintype "passive"))
    )
    (net (code "124") (name "Net-(V2-B)") (class "Default")
      (node (ref "R14") (pin "2") (pinfunction "2_2") (pintype "passive"))
      (node (ref "V2") (pin "1") (pinfunction "B_1") (pintype "passive"))
    )
    (net (code "125") (name "Net-(V2-C)") (class "Default")
      (node (ref "R11") (pin "1") (pinfunction "1_1") (pintype "passive"))
      (node (ref "R13") (pin "1") (pinfunction "1_1") (pintype "passive"))
      (node (ref "V2") (pin "3") (pinfunction "C_3") (pintype "passive"))
    )
    (net (code "126") (name "VCC5V") (class "Default")
      (node (ref "C22") (pin "2") (pinfunction "2_2") (pintype "passive"))
      (node (ref "D11") (pin "2") (pinfunction "K_2") (pintype "passive"))
      (node (ref "D15") (pin "2") (pinfunction "K_2") (pintype "passive"))
      (node (ref "F4") (pin "2") (pinfunction "2_2") (pintype "passive"))
      (node (ref "IC1") (pin "8") (pinfunction "Vdd_8") (pintype "passive"))
      (node (ref "IC2") (pin "1") (pinfunction "VIN_1") (pintype "passive"))
      (node (ref "IC2") (pin "3") (pinfunction "EN_3") (pintype "passive"))
      (node (ref "Q2") (pin "2") (pinfunction "S_2") (pintype "passive"))
      (node (ref "Q5") (pin "3") (pinfunction "C_3") (pintype "passive"))
      (node (ref "Q6") (pin "3") (pinfunction "C_3") (pintype "passive"))
      (node (ref "Q7") (pin "3") (pinfunction "C_3") (pintype "passive"))
      (node (ref "Q8") (pin "3") (pinfunction "C_3") (pintype "passive"))
      (node (ref "R11") (pin "2") (pinfunction "2_2") (pintype "passive"))
      (node (ref "R27") (pin "2") (pinfunction "2_2") (pintype "passive"))
      (node (ref "R4") (pin "2") (pinfunction "2_2") (pintype "passive"))
      (node (ref "R48") (pin "1") (pinfunction "1_1") (pintype "passive"))
      (node (ref "R51") (pin "1") (pinfunction "1_1") (pintype "passive"))
      (node (ref "R8") (pin "2") (pinfunction "2_2") (pintype "passive"))
      (node (ref "R9") (pin "1") (pinfunction "1_1") (pintype "passive"))
      (node (ref "RL1") (pin "2") (pinfunction "2_2") (pintype "passive"))
      (node (ref "RL2") (pin "2") (pinfunction "2_2") (pintype "passive"))
    )
    (net (code "127") (name "VRTC") (class "Default")
      (node (ref "R55") (pin "2") (pinfunction "2_2") (pintype "passive"))
      (node (ref "U11") (pin "1") (pinfunction "VBAT_1") (pintype "passive"))
    )
    (net (code "128") (name "unconnected-(U5-ANT-Pad12)") (class "Default")
      (node (ref "U5") (pin "12") (pinfunction "ANT_12") (pintype "passive+no_connect"))
    )
    (net (code "129") (name "unconnected-(U5-CLK-Pad15)") (class "Default")
      (node (ref "U5") (pin "15") (pinfunction "CLK_15") (pintype "passive+no_connect"))
    )
    (net (code "130") (name "unconnected-(U5-DIO-Pad14)") (class "Default")
      (node (ref "U5") (pin "14") (pinfunction "DIO_14") (pintype "passive+no_connect"))
    )
    (net (code "131") (name "unconnected-(U5-GND-Pad11)") (class "Default")
      (node (ref "U5") (pin "11") (pinfunction "GND_11") (pintype "passive+no_connect"))
    )
    (net (code "132") (name "unconnected-(U5-GND-Pad13)") (class "Default")
      (node (ref "U5") (pin "13") (pinfunction "GND_13") (pintype "passive+no_connect"))
    )
    (net (code "133") (name "unconnected-(U5-GND-Pad16)") (class "Default")
      (node (ref "U5") (pin "16") (pinfunction "GND_16") (pintype "passive+no_connect"))
    )
    (net (code "134") (name "unconnected-(U5-GPIO3-Pad3)") (class "Default")
      (node (ref "U5") (pin "3") (pinfunction "GPIO3_3") (pintype "passive+no_connect"))
    )
    (net (code "135") (name "unconnected-(U11-PA4{slash}SPI1_NSS{slash}_USART2_CK{slash}ADC12_IN4-Pad20)") (class "Default")
      (node (ref "U11") (pin "20") (pinfunction "PA4/SPI1_NSS/_USART2_CK/ADC12_IN4_20") (pintype "passive+no_connect"))
    )
    (net (code "136") (name "unconnected-(U11-PA5{slash}SPI1_SCK_{slash}ADC12_IN5-Pad21)") (class "Default")
      (node (ref "U11") (pin "21") (pinfunction "PA5/SPI1_SCK_/ADC12_IN5_21") (pintype "passive+no_connect"))
    )
    (net (code "137") (name "unconnected-(U11-PA8{slash}USART1_CK{slash}TIM1_CH1{slash}MCO-Pad41)") (class "Default")
      (node (ref "U11") (pin "41") (pinfunction "PA8/USART1_CK/TIM1_CH1/MCO_41") (pintype "passive+no_connect"))
    )
    (net (code "138") (name "unconnected-(U11-PA15{slash}JTDI{slash}TIM2_CH1_CH1{slash}_SPI1_NSS-Pad50)") (class "Default")
      (node (ref "U11") (pin "50") (pinfunction "PA15/JTDI/TIM2_CH1_CH1/_SPI1_NSS_50") (pintype "passive+no_connect"))
    )
    (net (code "139") (name "unconnected-(U11-PB8{slash}I2C_1_SCL{slash}_CAN_RX{slash}TIM4_CH3-Pad61)") (class "Default")
      (node (ref "U11") (pin "61") (pinfunction "PB8/I2C_1_SCL/_CAN_RX/TIM4_CH3_61") (pintype "passive+no_connect"))
    )
    (net (code "140") (name "unconnected-(U11-PB9{slash}I2C_1_SDA{slash}CAN_TX{slash}TIM4_CH4-Pad62)") (class "Default")
      (node (ref "U11") (pin "62") (pinfunction "PB9/I2C_1_SDA/CAN_TX/TIM4_CH4_62") (pintype "passive+no_connect"))
    )
    (net (code "141") (name "unconnected-(U11-PC6{slash}TIM3_CH1-Pad37)") (class "Default")
      (node (ref "U11") (pin "37") (pinfunction "PC6/TIM3_CH1_37") (pintype "passive+no_connect"))
    )
    (net (code "142") (name "unconnected-(U11-PC7{slash}TIM3_CH2-Pad38)") (class "Default")
      (node (ref "U11") (pin "38") (pinfunction "PC7/TIM3_CH2_38") (pintype "passive+no_connect"))
    )
    (net (code "143") (name "unconnected-(U11-PC8{slash}TIM3_CH3-Pad39)") (class "Default")
      (node (ref "U11") (pin "39") (pinfunction "PC8/TIM3_CH3_39") (pintype "passive+no_connect"))
    )
    (net (code "144") (name "unconnected-(U11-PC9{slash}TIM3_CH4-Pad40)") (class "Default")
      (node (ref "U11") (pin "40") (pinfunction "PC9/TIM3_CH4_40") (pintype "passive+no_connect"))
    )
    (net (code "145") (name "unconnected-(U11-PC10{slash}USART3_TX-Pad51)") (class "Default")
      (node (ref "U11") (pin "51") (pinfunction "PC10/USART3_TX_51") (pintype "passive+no_connect"))
    )
    (net (code "146") (name "unconnected-(U11-PC11{slash}USART3_RX-Pad52)") (class "Default")
      (node (ref "U11") (pin "52") (pinfunction "PC11/USART3_RX_52") (pintype "passive+no_connect"))
    )
    (net (code "147") (name "unconnected-(U11-PC13{slash}TAMPER-RTC-Pad2)") (class "Default")
      (node (ref "U11") (pin "2") (pinfunction "PC13/TAMPER-RTC_2") (pintype "passive+no_connect"))
    )
  )
)
